# Charge_station.net
KiCad netlist of a schematic drawn in Altium Designer
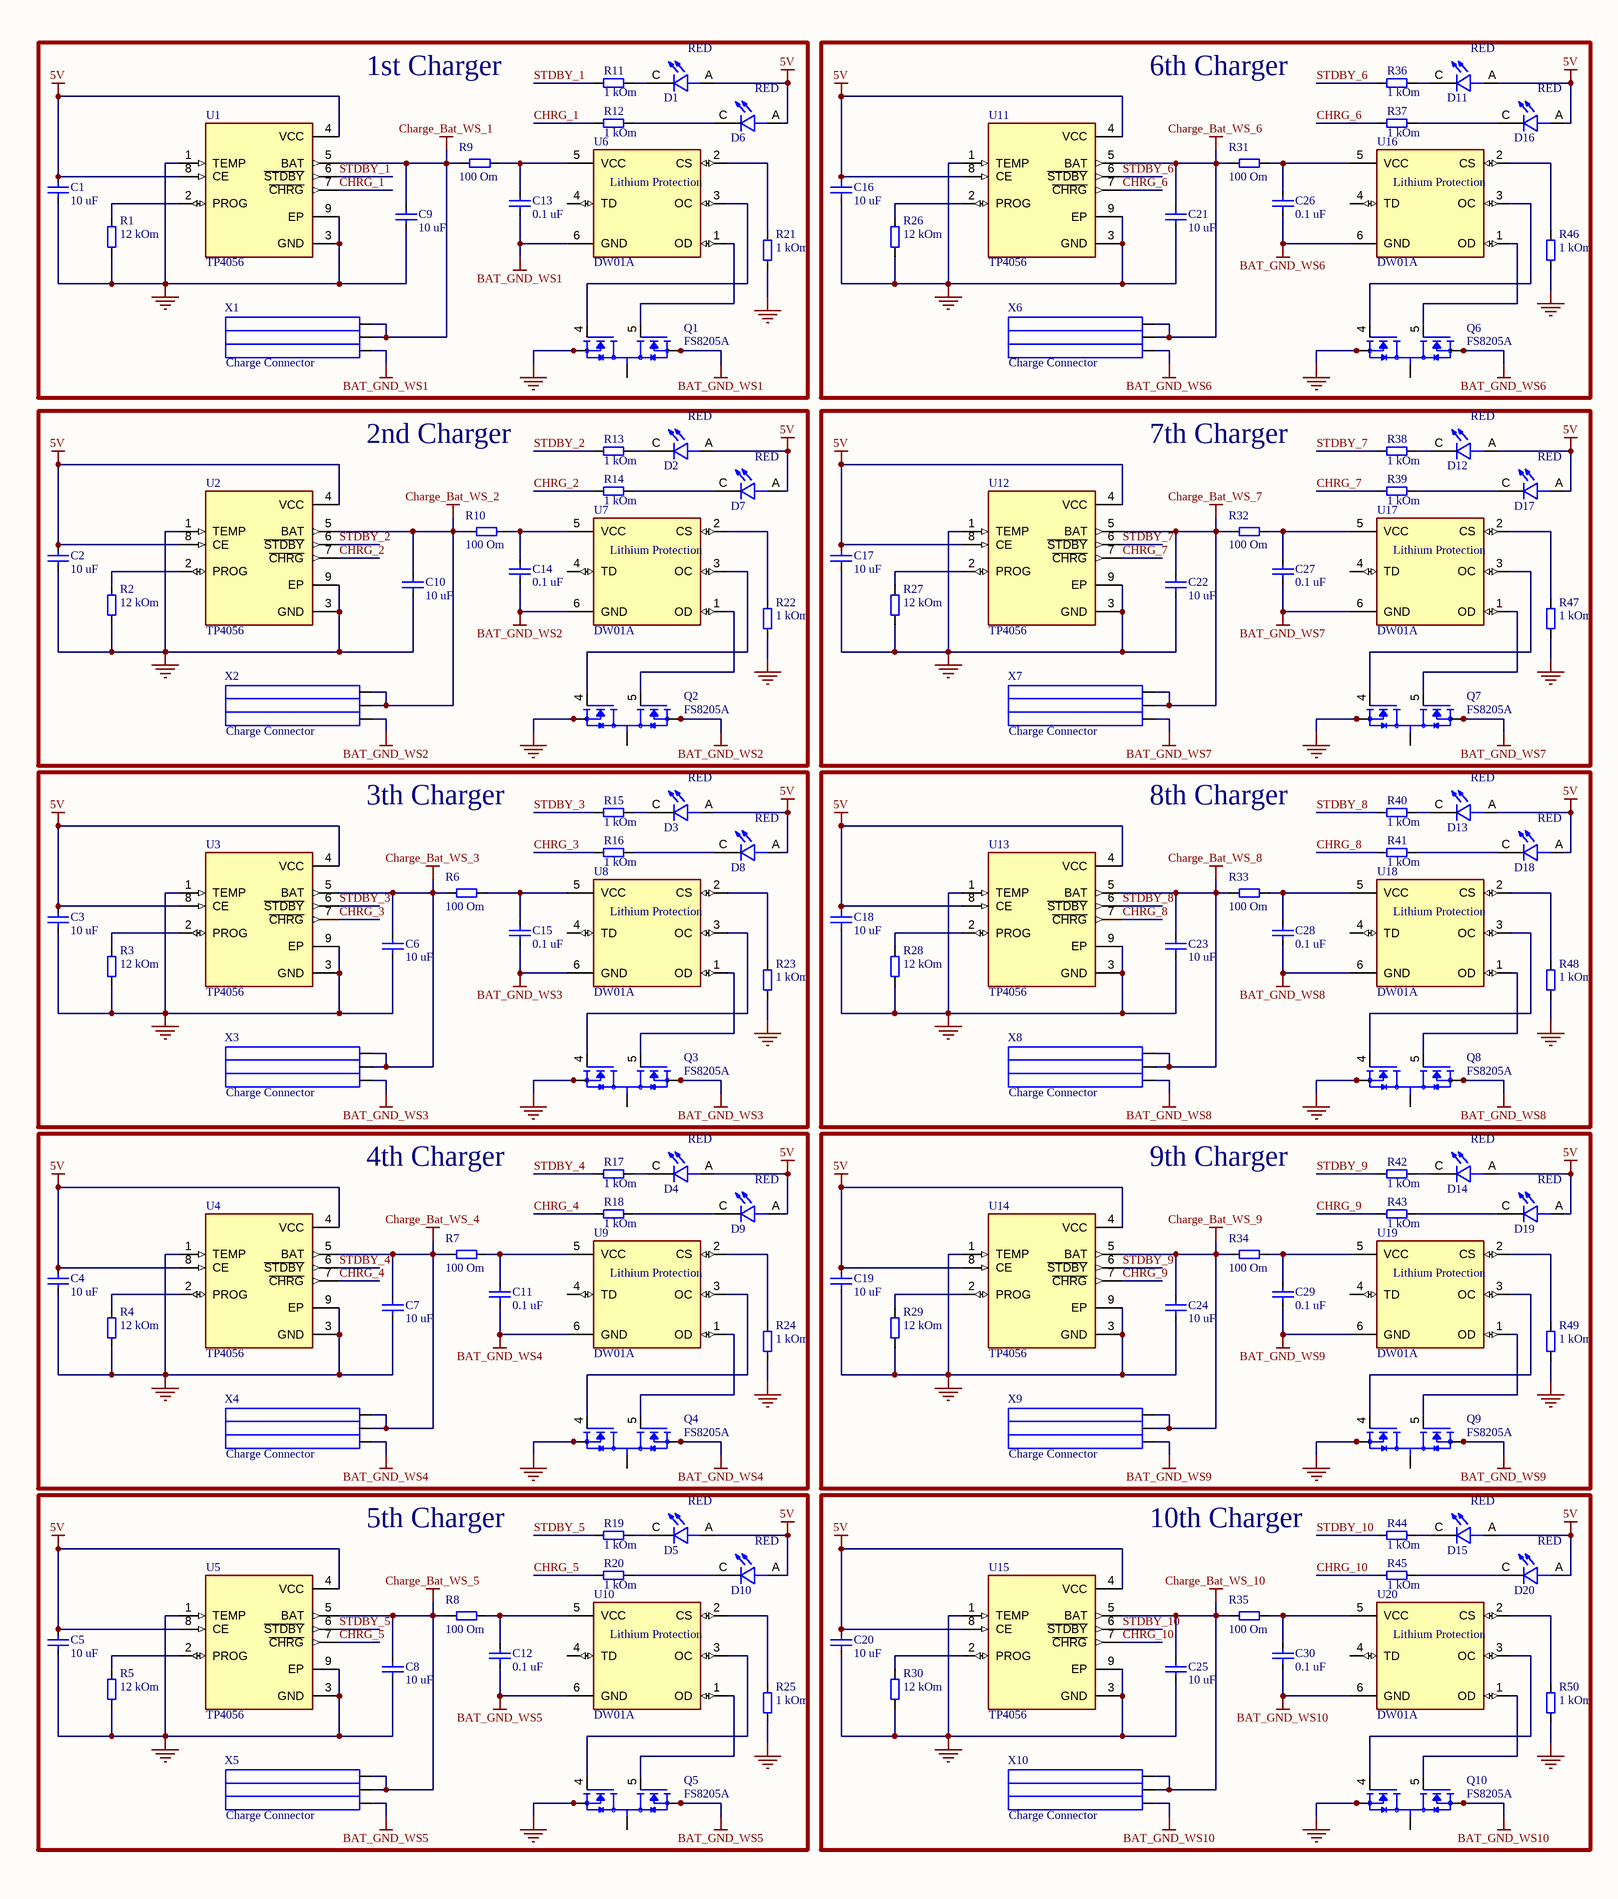
[diagram p0: Charge_station.SchDoc, left]
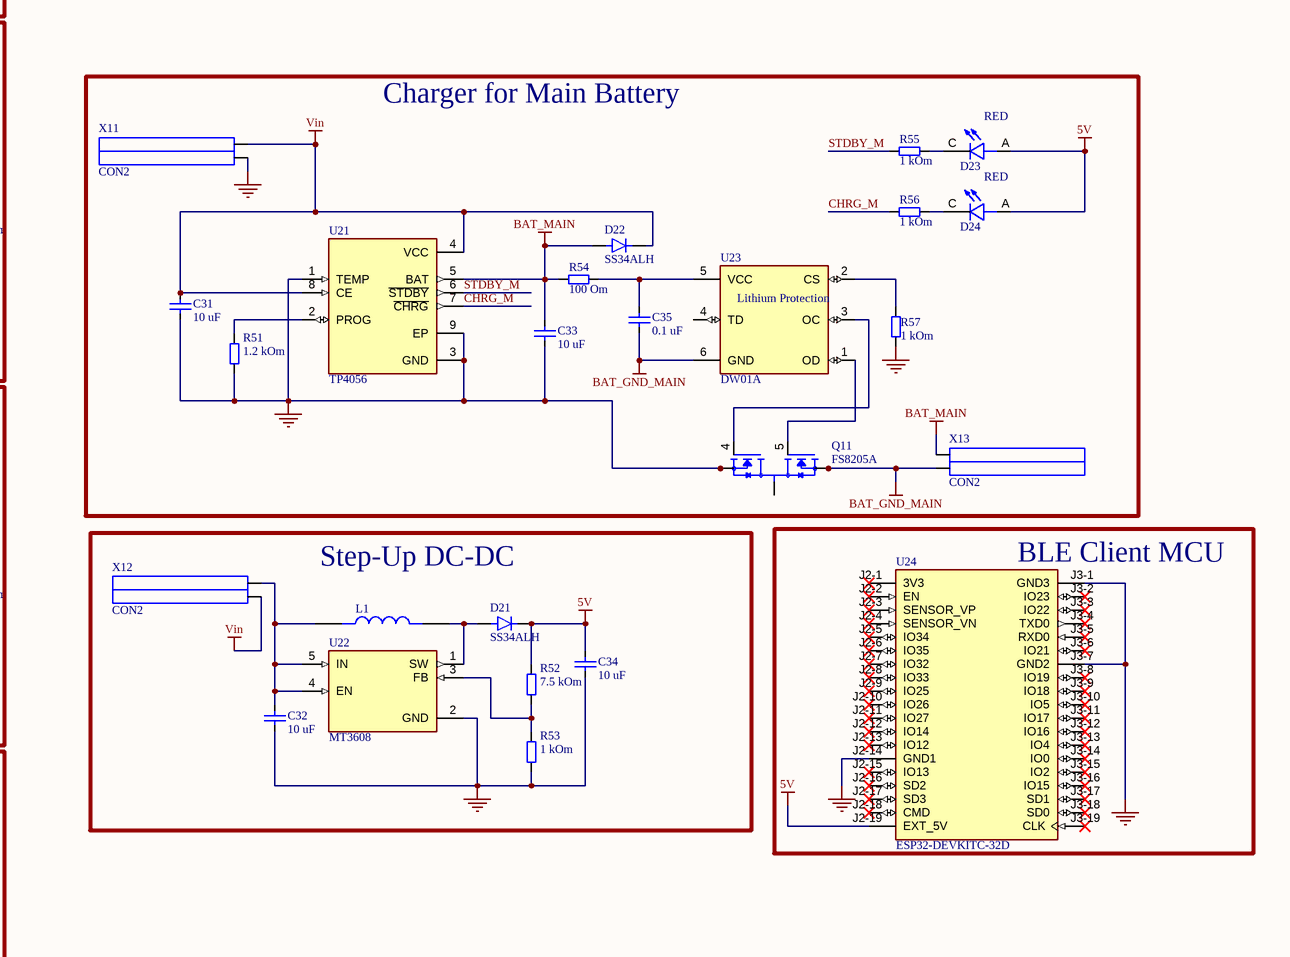
[diagram p1: Charge_station.SchDoc, right]

(export (version "E")
  (design (tool "Eeschema 10.0.6"))
  (components
    (comp (ref "C1")
      (value "10 uF")
      (footprint "CAPC1608X90N")
      (fields
        (field (name "MANUFACTURERPARTNUMBER") "GRM188R61C106MAAL")
        (field (name "MANUFACTURER") "muRata")
        (field (name "Comment") "STD_CAP")
        (field (name "AUTHORCREATION_COMP") "altium_lib_sch_p")
        (field (name "AUTHORMODIFICATION_COMP") "altium_lib_sch_p")
      )
      (libsource (lib "Altium_lib") (part "STD_CAP"))
    )
    (comp (ref "C2")
      (value "10 uF")
      (footprint "CAPC1608X90N")
      (fields
        (field (name "MANUFACTURERPARTNUMBER") "GRM188R61C106MAAL")
        (field (name "MANUFACTURER") "muRata")
        (field (name "Comment") "STD_CAP")
        (field (name "AUTHORCREATION_COMP") "altium_lib_sch_p")
        (field (name "AUTHORMODIFICATION_COMP") "altium_lib_sch_p")
      )
      (libsource (lib "Altium_lib") (part "STD_CAP"))
    )
    (comp (ref "C3")
      (value "10 uF")
      (footprint "CAPC1608X90N")
      (fields
        (field (name "MANUFACTURERPARTNUMBER") "GRM188R61C106MAAL")
        (field (name "MANUFACTURER") "muRata")
        (field (name "Comment") "STD_CAP")
        (field (name "AUTHORCREATION_COMP") "altium_lib_sch_p")
        (field (name "AUTHORMODIFICATION_COMP") "altium_lib_sch_p")
      )
      (libsource (lib "Altium_lib") (part "STD_CAP"))
    )
    (comp (ref "C4")
      (value "10 uF")
      (footprint "CAPC1608X90N")
      (fields
        (field (name "MANUFACTURERPARTNUMBER") "GRM188R61C106MAAL")
        (field (name "MANUFACTURER") "muRata")
        (field (name "Comment") "STD_CAP")
        (field (name "AUTHORCREATION_COMP") "altium_lib_sch_p")
        (field (name "AUTHORMODIFICATION_COMP") "altium_lib_sch_p")
      )
      (libsource (lib "Altium_lib") (part "STD_CAP"))
    )
    (comp (ref "C5")
      (value "10 uF")
      (footprint "CAPC1608X90N")
      (fields
        (field (name "MANUFACTURERPARTNUMBER") "GRM188R61C106MAAL")
        (field (name "MANUFACTURER") "muRata")
        (field (name "Comment") "STD_CAP")
        (field (name "AUTHORCREATION_COMP") "altium_lib_sch_p")
        (field (name "AUTHORMODIFICATION_COMP") "altium_lib_sch_p")
      )
      (libsource (lib "Altium_lib") (part "STD_CAP"))
    )
    (comp (ref "C6")
      (value "10 uF")
      (footprint "CAPC1608X90N")
      (fields
        (field (name "MANUFACTURERPARTNUMBER") "GRM188R61C106MAAL")
        (field (name "MANUFACTURER") "muRata")
        (field (name "Comment") "STD_CAP")
        (field (name "AUTHORCREATION_COMP") "altium_lib_sch_p")
        (field (name "AUTHORMODIFICATION_COMP") "altium_lib_sch_p")
      )
      (libsource (lib "Altium_lib") (part "STD_CAP"))
    )
    (comp (ref "C7")
      (value "10 uF")
      (footprint "CAPC1608X90N")
      (fields
        (field (name "MANUFACTURERPARTNUMBER") "GRM188R61C106MAAL")
        (field (name "MANUFACTURER") "muRata")
        (field (name "Comment") "STD_CAP")
        (field (name "AUTHORCREATION_COMP") "altium_lib_sch_p")
        (field (name "AUTHORMODIFICATION_COMP") "altium_lib_sch_p")
      )
      (libsource (lib "Altium_lib") (part "STD_CAP"))
    )
    (comp (ref "C8")
      (value "10 uF")
      (footprint "CAPC1608X90N")
      (fields
        (field (name "MANUFACTURERPARTNUMBER") "GRM188R61C106MAAL")
        (field (name "MANUFACTURER") "muRata")
        (field (name "Comment") "STD_CAP")
        (field (name "AUTHORCREATION_COMP") "altium_lib_sch_p")
        (field (name "AUTHORMODIFICATION_COMP") "altium_lib_sch_p")
      )
      (libsource (lib "Altium_lib") (part "STD_CAP"))
    )
    (comp (ref "C9")
      (value "10 uF")
      (footprint "CAPC1608X90N")
      (fields
        (field (name "MANUFACTURERPARTNUMBER") "GRM188R61C106MAAL")
        (field (name "MANUFACTURER") "muRata")
        (field (name "Comment") "STD_CAP")
        (field (name "AUTHORCREATION_COMP") "altium_lib_sch_p")
        (field (name "AUTHORMODIFICATION_COMP") "altium_lib_sch_p")
      )
      (libsource (lib "Altium_lib") (part "STD_CAP"))
    )
    (comp (ref "C10")
      (value "10 uF")
      (footprint "CAPC1608X90N")
      (fields
        (field (name "MANUFACTURERPARTNUMBER") "GRM188R61C106MAAL")
        (field (name "MANUFACTURER") "muRata")
        (field (name "Comment") "STD_CAP")
        (field (name "AUTHORCREATION_COMP") "altium_lib_sch_p")
        (field (name "AUTHORMODIFICATION_COMP") "altium_lib_sch_p")
      )
      (libsource (lib "Altium_lib") (part "STD_CAP"))
    )
    (comp (ref "C11")
      (value "0.1 uF")
      (footprint "CAPC1608X90N")
      (fields
        (field (name "MANUFACTURERPARTNUMBER") "C1608X7R1H104K")
        (field (name "MANUFACTURER") "TDK")
        (field (name "Comment") "STD_CAP")
        (field (name "AUTHORCREATION_COMP") "anosova")
        (field (name "AUTHORMODIFICATION_COMP") "anosova")
      )
      (libsource (lib "Altium_lib") (part "STD_CAP"))
    )
    (comp (ref "C12")
      (value "0.1 uF")
      (footprint "CAPC1608X90N")
      (fields
        (field (name "MANUFACTURERPARTNUMBER") "C1608X7R1H104K")
        (field (name "MANUFACTURER") "TDK")
        (field (name "Comment") "STD_CAP")
        (field (name "AUTHORCREATION_COMP") "anosova")
        (field (name "AUTHORMODIFICATION_COMP") "anosova")
      )
      (libsource (lib "Altium_lib") (part "STD_CAP"))
    )
    (comp (ref "C13")
      (value "0.1 uF")
      (footprint "CAPC1608X90N")
      (fields
        (field (name "MANUFACTURERPARTNUMBER") "C1608X7R1H104K")
        (field (name "MANUFACTURER") "TDK")
        (field (name "Comment") "STD_CAP")
        (field (name "AUTHORCREATION_COMP") "anosova")
        (field (name "AUTHORMODIFICATION_COMP") "anosova")
      )
      (libsource (lib "Altium_lib") (part "STD_CAP"))
    )
    (comp (ref "C14")
      (value "0.1 uF")
      (footprint "CAPC1608X90N")
      (fields
        (field (name "MANUFACTURERPARTNUMBER") "C1608X7R1H104K")
        (field (name "MANUFACTURER") "TDK")
        (field (name "Comment") "STD_CAP")
        (field (name "AUTHORCREATION_COMP") "anosova")
        (field (name "AUTHORMODIFICATION_COMP") "anosova")
      )
      (libsource (lib "Altium_lib") (part "STD_CAP"))
    )
    (comp (ref "C15")
      (value "0.1 uF")
      (footprint "CAPC1608X90N")
      (fields
        (field (name "MANUFACTURERPARTNUMBER") "C1608X7R1H104K")
        (field (name "MANUFACTURER") "TDK")
        (field (name "Comment") "STD_CAP")
        (field (name "AUTHORCREATION_COMP") "anosova")
        (field (name "AUTHORMODIFICATION_COMP") "anosova")
      )
      (libsource (lib "Altium_lib") (part "STD_CAP"))
    )
    (comp (ref "C16")
      (value "10 uF")
      (footprint "CAPC1608X90N")
      (fields
        (field (name "MANUFACTURERPARTNUMBER") "GRM188R61C106MAAL")
        (field (name "MANUFACTURER") "muRata")
        (field (name "Comment") "STD_CAP")
        (field (name "AUTHORCREATION_COMP") "altium_lib_sch_p")
        (field (name "AUTHORMODIFICATION_COMP") "altium_lib_sch_p")
      )
      (libsource (lib "Altium_lib") (part "STD_CAP"))
    )
    (comp (ref "C17")
      (value "10 uF")
      (footprint "CAPC1608X90N")
      (fields
        (field (name "MANUFACTURERPARTNUMBER") "GRM188R61C106MAAL")
        (field (name "MANUFACTURER") "muRata")
        (field (name "Comment") "STD_CAP")
        (field (name "AUTHORCREATION_COMP") "altium_lib_sch_p")
        (field (name "AUTHORMODIFICATION_COMP") "altium_lib_sch_p")
      )
      (libsource (lib "Altium_lib") (part "STD_CAP"))
    )
    (comp (ref "C18")
      (value "10 uF")
      (footprint "CAPC1608X90N")
      (fields
        (field (name "MANUFACTURERPARTNUMBER") "GRM188R61C106MAAL")
        (field (name "MANUFACTURER") "muRata")
        (field (name "Comment") "STD_CAP")
        (field (name "AUTHORCREATION_COMP") "altium_lib_sch_p")
        (field (name "AUTHORMODIFICATION_COMP") "altium_lib_sch_p")
      )
      (libsource (lib "Altium_lib") (part "STD_CAP"))
    )
    (comp (ref "C19")
      (value "10 uF")
      (footprint "CAPC1608X90N")
      (fields
        (field (name "MANUFACTURERPARTNUMBER") "GRM188R61C106MAAL")
        (field (name "MANUFACTURER") "muRata")
        (field (name "Comment") "STD_CAP")
        (field (name "AUTHORCREATION_COMP") "altium_lib_sch_p")
        (field (name "AUTHORMODIFICATION_COMP") "altium_lib_sch_p")
      )
      (libsource (lib "Altium_lib") (part "STD_CAP"))
    )
    (comp (ref "C20")
      (value "10 uF")
      (footprint "CAPC1608X90N")
      (fields
        (field (name "MANUFACTURERPARTNUMBER") "GRM188R61C106MAAL")
        (field (name "MANUFACTURER") "muRata")
        (field (name "Comment") "STD_CAP")
        (field (name "AUTHORCREATION_COMP") "altium_lib_sch_p")
        (field (name "AUTHORMODIFICATION_COMP") "altium_lib_sch_p")
      )
      (libsource (lib "Altium_lib") (part "STD_CAP"))
    )
    (comp (ref "C21")
      (value "10 uF")
      (footprint "CAPC1608X90N")
      (fields
        (field (name "MANUFACTURERPARTNUMBER") "GRM188R61C106MAAL")
        (field (name "MANUFACTURER") "muRata")
        (field (name "Comment") "STD_CAP")
        (field (name "AUTHORCREATION_COMP") "altium_lib_sch_p")
        (field (name "AUTHORMODIFICATION_COMP") "altium_lib_sch_p")
      )
      (libsource (lib "Altium_lib") (part "STD_CAP"))
    )
    (comp (ref "C22")
      (value "10 uF")
      (footprint "CAPC1608X90N")
      (fields
        (field (name "MANUFACTURERPARTNUMBER") "GRM188R61C106MAAL")
        (field (name "MANUFACTURER") "muRata")
        (field (name "Comment") "STD_CAP")
        (field (name "AUTHORCREATION_COMP") "altium_lib_sch_p")
        (field (name "AUTHORMODIFICATION_COMP") "altium_lib_sch_p")
      )
      (libsource (lib "Altium_lib") (part "STD_CAP"))
    )
    (comp (ref "C23")
      (value "10 uF")
      (footprint "CAPC1608X90N")
      (fields
        (field (name "MANUFACTURERPARTNUMBER") "GRM188R61C106MAAL")
        (field (name "MANUFACTURER") "muRata")
        (field (name "Comment") "STD_CAP")
        (field (name "AUTHORCREATION_COMP") "altium_lib_sch_p")
        (field (name "AUTHORMODIFICATION_COMP") "altium_lib_sch_p")
      )
      (libsource (lib "Altium_lib") (part "STD_CAP"))
    )
    (comp (ref "C24")
      (value "10 uF")
      (footprint "CAPC1608X90N")
      (fields
        (field (name "MANUFACTURERPARTNUMBER") "GRM188R61C106MAAL")
        (field (name "MANUFACTURER") "muRata")
        (field (name "Comment") "STD_CAP")
        (field (name "AUTHORCREATION_COMP") "altium_lib_sch_p")
        (field (name "AUTHORMODIFICATION_COMP") "altium_lib_sch_p")
      )
      (libsource (lib "Altium_lib") (part "STD_CAP"))
    )
    (comp (ref "C25")
      (value "10 uF")
      (footprint "CAPC1608X90N")
      (fields
        (field (name "MANUFACTURERPARTNUMBER") "GRM188R61C106MAAL")
        (field (name "MANUFACTURER") "muRata")
        (field (name "Comment") "STD_CAP")
        (field (name "AUTHORCREATION_COMP") "altium_lib_sch_p")
        (field (name "AUTHORMODIFICATION_COMP") "altium_lib_sch_p")
      )
      (libsource (lib "Altium_lib") (part "STD_CAP"))
    )
    (comp (ref "C26")
      (value "0.1 uF")
      (footprint "CAPC1608X90N")
      (fields
        (field (name "MANUFACTURERPARTNUMBER") "C1608X7R1H104K")
        (field (name "MANUFACTURER") "TDK")
        (field (name "Comment") "STD_CAP")
        (field (name "AUTHORCREATION_COMP") "anosova")
        (field (name "AUTHORMODIFICATION_COMP") "anosova")
      )
      (libsource (lib "Altium_lib") (part "STD_CAP"))
    )
    (comp (ref "C27")
      (value "0.1 uF")
      (footprint "CAPC1608X90N")
      (fields
        (field (name "MANUFACTURERPARTNUMBER") "C1608X7R1H104K")
        (field (name "MANUFACTURER") "TDK")
        (field (name "Comment") "STD_CAP")
        (field (name "AUTHORCREATION_COMP") "anosova")
        (field (name "AUTHORMODIFICATION_COMP") "anosova")
      )
      (libsource (lib "Altium_lib") (part "STD_CAP"))
    )
    (comp (ref "C28")
      (value "0.1 uF")
      (footprint "CAPC1608X90N")
      (fields
        (field (name "MANUFACTURERPARTNUMBER") "C1608X7R1H104K")
        (field (name "MANUFACTURER") "TDK")
        (field (name "Comment") "STD_CAP")
        (field (name "AUTHORCREATION_COMP") "anosova")
        (field (name "AUTHORMODIFICATION_COMP") "anosova")
      )
      (libsource (lib "Altium_lib") (part "STD_CAP"))
    )
    (comp (ref "C29")
      (value "0.1 uF")
      (footprint "CAPC1608X90N")
      (fields
        (field (name "MANUFACTURERPARTNUMBER") "C1608X7R1H104K")
        (field (name "MANUFACTURER") "TDK")
        (field (name "Comment") "STD_CAP")
        (field (name "AUTHORCREATION_COMP") "anosova")
        (field (name "AUTHORMODIFICATION_COMP") "anosova")
      )
      (libsource (lib "Altium_lib") (part "STD_CAP"))
    )
    (comp (ref "C30")
      (value "0.1 uF")
      (footprint "CAPC1608X90N")
      (fields
        (field (name "MANUFACTURERPARTNUMBER") "C1608X7R1H104K")
        (field (name "MANUFACTURER") "TDK")
        (field (name "Comment") "STD_CAP")
        (field (name "AUTHORCREATION_COMP") "anosova")
        (field (name "AUTHORMODIFICATION_COMP") "anosova")
      )
      (libsource (lib "Altium_lib") (part "STD_CAP"))
    )
    (comp (ref "C31")
      (value "10 uF")
      (footprint "CAPC1608X90N")
      (fields
        (field (name "MANUFACTURERPARTNUMBER") "GRM188R61C106MAAL")
        (field (name "MANUFACTURER") "muRata")
        (field (name "Comment") "STD_CAP")
        (field (name "AUTHORCREATION_COMP") "altium_lib_sch_p")
        (field (name "AUTHORMODIFICATION_COMP") "altium_lib_sch_p")
      )
      (libsource (lib "Altium_lib") (part "STD_CAP"))
    )
    (comp (ref "C32")
      (value "10 uF")
      (footprint "CAPC2012X120N")
      (fields
        (field (name "MANUFACTURERPARTNUMBER") "GRM21BR71A106KE51L")
        (field (name "MANUFACTURER") "muRata")
        (field (name "Comment") "STD_CAP")
      )
      (libsource (lib "Altium_lib") (part "STD_CAP"))
    )
    (comp (ref "C33")
      (value "10 uF")
      (footprint "CAPC1608X90N")
      (fields
        (field (name "MANUFACTURERPARTNUMBER") "GRM188R61C106MAAL")
        (field (name "MANUFACTURER") "muRata")
        (field (name "Comment") "STD_CAP")
        (field (name "AUTHORCREATION_COMP") "altium_lib_sch_p")
        (field (name "AUTHORMODIFICATION_COMP") "altium_lib_sch_p")
      )
      (libsource (lib "Altium_lib") (part "STD_CAP"))
    )
    (comp (ref "C34")
      (value "10 uF")
      (footprint "CAPC2012X120N")
      (fields
        (field (name "MANUFACTURERPARTNUMBER") "GRM21BR71A106KE51L")
        (field (name "MANUFACTURER") "muRata")
        (field (name "Comment") "STD_CAP")
      )
      (libsource (lib "Altium_lib") (part "STD_CAP"))
    )
    (comp (ref "C35")
      (value "0.1 uF")
      (footprint "CAPC1608X90N")
      (fields
        (field (name "MANUFACTURERPARTNUMBER") "C1608X7R1H104K")
        (field (name "MANUFACTURER") "TDK")
        (field (name "Comment") "STD_CAP")
        (field (name "AUTHORCREATION_COMP") "anosova")
        (field (name "AUTHORMODIFICATION_COMP") "anosova")
      )
      (libsource (lib "Altium_lib") (part "STD_CAP"))
    )
    (comp (ref "D1")
      (value "7012X1")
      (footprint "LED_KPT-1608ZGC")
      (description "Red - LED Indication - Discrete 1.7V 0805 (2012 Metric)")
      (fields (field (name "MF") "VCC"))
      (libsource (lib "7012X1") (part "7012X1"))
    )
    (comp (ref "D2")
      (value "7012X1")
      (footprint "LED_KPT-1608ZGC")
      (description "Red - LED Indication - Discrete 1.7V 0805 (2012 Metric)")
      (fields (field (name "MF") "VCC"))
      (libsource (lib "7012X1") (part "7012X1"))
    )
    (comp (ref "D3")
      (value "7012X1")
      (footprint "LED_KPT-1608ZGC")
      (description "Red - LED Indication - Discrete 1.7V 0805 (2012 Metric)")
      (fields (field (name "MF") "VCC"))
      (libsource (lib "7012X1") (part "7012X1"))
    )
    (comp (ref "D4")
      (value "7012X1")
      (footprint "LED_KPT-1608ZGC")
      (description "Red - LED Indication - Discrete 1.7V 0805 (2012 Metric)")
      (fields (field (name "MF") "VCC"))
      (libsource (lib "7012X1") (part "7012X1"))
    )
    (comp (ref "D5")
      (value "7012X1")
      (footprint "LED_KPT-1608ZGC")
      (description "Red - LED Indication - Discrete 1.7V 0805 (2012 Metric)")
      (fields (field (name "MF") "VCC"))
      (libsource (lib "7012X1") (part "7012X1"))
    )
    (comp (ref "D6")
      (value "7012X1")
      (footprint "LED_KPT-1608ZGC")
      (description "Red - LED Indication - Discrete 1.7V 0805 (2012 Metric)")
      (fields (field (name "MF") "VCC"))
      (libsource (lib "7012X1") (part "7012X1"))
    )
    (comp (ref "D7")
      (value "7012X1")
      (footprint "LED_KPT-1608ZGC")
      (description "Red - LED Indication - Discrete 1.7V 0805 (2012 Metric)")
      (fields (field (name "MF") "VCC"))
      (libsource (lib "7012X1") (part "7012X1"))
    )
    (comp (ref "D8")
      (value "7012X1")
      (footprint "LED_KPT-1608ZGC")
      (description "Red - LED Indication - Discrete 1.7V 0805 (2012 Metric)")
      (fields (field (name "MF") "VCC"))
      (libsource (lib "7012X1") (part "7012X1"))
    )
    (comp (ref "D9")
      (value "7012X1")
      (footprint "LED_KPT-1608ZGC")
      (description "Red - LED Indication - Discrete 1.7V 0805 (2012 Metric)")
      (fields (field (name "MF") "VCC"))
      (libsource (lib "7012X1") (part "7012X1"))
    )
    (comp (ref "D10")
      (value "7012X1")
      (footprint "LED_KPT-1608ZGC")
      (description "Red - LED Indication - Discrete 1.7V 0805 (2012 Metric)")
      (fields (field (name "MF") "VCC"))
      (libsource (lib "7012X1") (part "7012X1"))
    )
    (comp (ref "D11")
      (value "7012X1")
      (footprint "LED_KPT-1608ZGC")
      (description "Red - LED Indication - Discrete 1.7V 0805 (2012 Metric)")
      (fields (field (name "MF") "VCC"))
      (libsource (lib "7012X1") (part "7012X1"))
    )
    (comp (ref "D12")
      (value "7012X1")
      (footprint "LED_KPT-1608ZGC")
      (description "Red - LED Indication - Discrete 1.7V 0805 (2012 Metric)")
      (fields (field (name "MF") "VCC"))
      (libsource (lib "7012X1") (part "7012X1"))
    )
    (comp (ref "D13")
      (value "7012X1")
      (footprint "LED_KPT-1608ZGC")
      (description "Red - LED Indication - Discrete 1.7V 0805 (2012 Metric)")
      (fields (field (name "MF") "VCC"))
      (libsource (lib "7012X1") (part "7012X1"))
    )
    (comp (ref "D14")
      (value "7012X1")
      (footprint "LED_KPT-1608ZGC")
      (description "Red - LED Indication - Discrete 1.7V 0805 (2012 Metric)")
      (fields (field (name "MF") "VCC"))
      (libsource (lib "7012X1") (part "7012X1"))
    )
    (comp (ref "D15")
      (value "7012X1")
      (footprint "LED_KPT-1608ZGC")
      (description "Red - LED Indication - Discrete 1.7V 0805 (2012 Metric)")
      (fields (field (name "MF") "VCC"))
      (libsource (lib "7012X1") (part "7012X1"))
    )
    (comp (ref "D16")
      (value "7012X1")
      (footprint "LED_KPT-1608ZGC")
      (description "Red - LED Indication - Discrete 1.7V 0805 (2012 Metric)")
      (fields (field (name "MF") "VCC"))
      (libsource (lib "7012X1") (part "7012X1"))
    )
    (comp (ref "D17")
      (value "7012X1")
      (footprint "LED_KPT-1608ZGC")
      (description "Red - LED Indication - Discrete 1.7V 0805 (2012 Metric)")
      (fields (field (name "MF") "VCC"))
      (libsource (lib "7012X1") (part "7012X1"))
    )
    (comp (ref "D18")
      (value "7012X1")
      (footprint "LED_KPT-1608ZGC")
      (description "Red - LED Indication - Discrete 1.7V 0805 (2012 Metric)")
      (fields (field (name "MF") "VCC"))
      (libsource (lib "7012X1") (part "7012X1"))
    )
    (comp (ref "D19")
      (value "7012X1")
      (footprint "LED_KPT-1608ZGC")
      (description "Red - LED Indication - Discrete 1.7V 0805 (2012 Metric)")
      (fields (field (name "MF") "VCC"))
      (libsource (lib "7012X1") (part "7012X1"))
    )
    (comp (ref "D20")
      (value "7012X1")
      (footprint "LED_KPT-1608ZGC")
      (description "Red - LED Indication - Discrete 1.7V 0805 (2012 Metric)")
      (fields (field (name "MF") "VCC"))
      (libsource (lib "7012X1") (part "7012X1"))
    )
    (comp (ref "D21")
      (value "SS34ALH")
      (footprint "SODFL5226X100N")
      (description "3A, 40V, Schottky Rectifier")
      (fields (field (name "MF") "Taiwan Semiconductor"))
      (libsource (lib "SCH_Wearing_sensor") (part "SS34ALH"))
    )
    (comp (ref "D22")
      (value "SS34ALH")
      (footprint "SODFL5226X100N")
      (description "3A, 40V, Schottky Rectifier")
      (fields (field (name "MF") "Taiwan Semiconductor"))
      (libsource (lib "SCH_Wearing_sensor") (part "SS34ALH"))
    )
    (comp (ref "D23")
      (value "7012X1")
      (footprint "LED_KPT-1608ZGC")
      (description "Red - LED Indication - Discrete 1.7V 0805 (2012 Metric)")
      (fields (field (name "MF") "VCC"))
      (libsource (lib "7012X1") (part "7012X1"))
    )
    (comp (ref "D24")
      (value "7012X1")
      (footprint "LED_KPT-1608ZGC")
      (description "Red - LED Indication - Discrete 1.7V 0805 (2012 Metric)")
      (fields (field (name "MF") "VCC"))
      (libsource (lib "7012X1") (part "7012X1"))
    )
    (comp (ref "L1")
      (value "B82464G4223M000")
      (footprint "IND_B82464G4223M000")
      (fields (field (name "MF") "TDK ELECTRONICS"))
      (libsource (lib "SCH_Wearing_sensor") (part "B82464G4223M000"))
    )
    (comp (ref "Q1")
      (value "FS8205A")
      (footprint "SOP65P640X120-8N")
      (fields (field (name "MF") "Fortune Semiconductor"))
      (libsource (lib "SCH_Wearing_sensor") (part "FS8205A"))
    )
    (comp (ref "Q2")
      (value "FS8205A")
      (footprint "SOP65P640X120-8N")
      (fields (field (name "MF") "Fortune Semiconductor"))
      (libsource (lib "SCH_Wearing_sensor") (part "FS8205A"))
    )
    (comp (ref "Q3")
      (value "FS8205A")
      (footprint "SOP65P640X120-8N")
      (fields (field (name "MF") "Fortune Semiconductor"))
      (libsource (lib "SCH_Wearing_sensor") (part "FS8205A"))
    )
    (comp (ref "Q4")
      (value "FS8205A")
      (footprint "SOP65P640X120-8N")
      (fields (field (name "MF") "Fortune Semiconductor"))
      (libsource (lib "SCH_Wearing_sensor") (part "FS8205A"))
    )
    (comp (ref "Q5")
      (value "FS8205A")
      (footprint "SOP65P640X120-8N")
      (fields (field (name "MF") "Fortune Semiconductor"))
      (libsource (lib "SCH_Wearing_sensor") (part "FS8205A"))
    )
    (comp (ref "Q6")
      (value "FS8205A")
      (footprint "SOP65P640X120-8N")
      (fields (field (name "MF") "Fortune Semiconductor"))
      (libsource (lib "SCH_Wearing_sensor") (part "FS8205A"))
    )
    (comp (ref "Q7")
      (value "FS8205A")
      (footprint "SOP65P640X120-8N")
      (fields (field (name "MF") "Fortune Semiconductor"))
      (libsource (lib "SCH_Wearing_sensor") (part "FS8205A"))
    )
    (comp (ref "Q8")
      (value "FS8205A")
      (footprint "SOP65P640X120-8N")
      (fields (field (name "MF") "Fortune Semiconductor"))
      (libsource (lib "SCH_Wearing_sensor") (part "FS8205A"))
    )
    (comp (ref "Q9")
      (value "FS8205A")
      (footprint "SOP65P640X120-8N")
      (fields (field (name "MF") "Fortune Semiconductor"))
      (libsource (lib "SCH_Wearing_sensor") (part "FS8205A"))
    )
    (comp (ref "Q10")
      (value "FS8205A")
      (footprint "SOP65P640X120-8N")
      (fields (field (name "MF") "Fortune Semiconductor"))
      (libsource (lib "SCH_Wearing_sensor") (part "FS8205A"))
    )
    (comp (ref "Q11")
      (value "FS8205A")
      (footprint "SOP65P640X120-8N")
      (fields (field (name "MF") "Fortune Semiconductor"))
      (libsource (lib "SCH_Wearing_sensor") (part "FS8205A"))
    )
    (comp (ref "R1")
      (value "12 kOm")
      (footprint "RESC1608X50AN")
      (fields
        (field (name "MANUFACTURERPARTNUMBER") "RC0603JR-0712KL")
        (field (name "MANUFACTURER") "Yageo")
        (field (name "Comment") "STD_RES")
      )
      (libsource (lib "") (part "STD_RES_2"))
    )
    (comp (ref "R2")
      (value "12 kOm")
      (footprint "RESC1608X50AN")
      (fields
        (field (name "MANUFACTURERPARTNUMBER") "RC0603JR-0712KL")
        (field (name "MANUFACTURER") "Yageo")
        (field (name "Comment") "STD_RES")
      )
      (libsource (lib "") (part "STD_RES_2"))
    )
    (comp (ref "R3")
      (value "12 kOm")
      (footprint "RESC1608X50AN")
      (fields
        (field (name "MANUFACTURERPARTNUMBER") "RC0603JR-0712KL")
        (field (name "MANUFACTURER") "Yageo")
        (field (name "Comment") "STD_RES")
      )
      (libsource (lib "") (part "STD_RES_2"))
    )
    (comp (ref "R4")
      (value "12 kOm")
      (footprint "RESC1608X50AN")
      (fields
        (field (name "MANUFACTURERPARTNUMBER") "RC0603JR-0712KL")
        (field (name "MANUFACTURER") "Yageo")
        (field (name "Comment") "STD_RES")
      )
      (libsource (lib "") (part "STD_RES_2"))
    )
    (comp (ref "R5")
      (value "12 kOm")
      (footprint "RESC1608X50AN")
      (fields
        (field (name "MANUFACTURERPARTNUMBER") "RC0603JR-0712KL")
        (field (name "MANUFACTURER") "Yageo")
        (field (name "Comment") "STD_RES")
      )
      (libsource (lib "") (part "STD_RES_2"))
    )
    (comp (ref "R6")
      (value "100 Om")
      (footprint "RESC1608X50AN")
      (fields
        (field (name "MANUFACTURERPARTNUMBER") "RC0603FR-07100RL")
        (field (name "MANUFACTURER") "Yageo")
        (field (name "Comment") "STD_RES")
      )
      (libsource (lib "Altium_lib") (part "STD_RES"))
    )
    (comp (ref "R7")
      (value "100 Om")
      (footprint "RESC1608X50AN")
      (fields
        (field (name "MANUFACTURERPARTNUMBER") "RC0603FR-07100RL")
        (field (name "MANUFACTURER") "Yageo")
        (field (name "Comment") "STD_RES")
      )
      (libsource (lib "Altium_lib") (part "STD_RES"))
    )
    (comp (ref "R8")
      (value "100 Om")
      (footprint "RESC1608X50AN")
      (fields
        (field (name "MANUFACTURERPARTNUMBER") "RC0603FR-07100RL")
        (field (name "MANUFACTURER") "Yageo")
        (field (name "Comment") "STD_RES")
      )
      (libsource (lib "Altium_lib") (part "STD_RES"))
    )
    (comp (ref "R9")
      (value "100 Om")
      (footprint "RESC1608X50AN")
      (fields
        (field (name "MANUFACTURERPARTNUMBER") "RC0603FR-07100RL")
        (field (name "MANUFACTURER") "Yageo")
        (field (name "Comment") "STD_RES")
      )
      (libsource (lib "Altium_lib") (part "STD_RES"))
    )
    (comp (ref "R10")
      (value "100 Om")
      (footprint "RESC1608X50AN")
      (fields
        (field (name "MANUFACTURERPARTNUMBER") "RC0603FR-07100RL")
        (field (name "MANUFACTURER") "Yageo")
        (field (name "Comment") "STD_RES")
      )
      (libsource (lib "Altium_lib") (part "STD_RES"))
    )
    (comp (ref "R11")
      (value "1 kOm")
      (footprint "R0603")
      (fields
        (field (name "MANUFACTURERPARTNUMBER") "RC0603FR-071K00L")
        (field (name "MANUFACTURER") "Yageo")
        (field (name "Comment") "STD_RES")
      )
      (libsource (lib "") (part "STD_RES_1"))
    )
    (comp (ref "R12")
      (value "1 kOm")
      (footprint "R0603")
      (fields
        (field (name "MANUFACTURERPARTNUMBER") "RC0603FR-071K00L")
        (field (name "MANUFACTURER") "Yageo")
        (field (name "Comment") "STD_RES")
      )
      (libsource (lib "") (part "STD_RES_1"))
    )
    (comp (ref "R13")
      (value "1 kOm")
      (footprint "R0603")
      (fields
        (field (name "MANUFACTURERPARTNUMBER") "RC0603FR-071K00L")
        (field (name "MANUFACTURER") "Yageo")
        (field (name "Comment") "STD_RES")
      )
      (libsource (lib "") (part "STD_RES_1"))
    )
    (comp (ref "R14")
      (value "1 kOm")
      (footprint "R0603")
      (fields
        (field (name "MANUFACTURERPARTNUMBER") "RC0603FR-071K00L")
        (field (name "MANUFACTURER") "Yageo")
        (field (name "Comment") "STD_RES")
      )
      (libsource (lib "") (part "STD_RES_1"))
    )
    (comp (ref "R15")
      (value "1 kOm")
      (footprint "R0603")
      (fields
        (field (name "MANUFACTURERPARTNUMBER") "RC0603FR-071K00L")
        (field (name "MANUFACTURER") "Yageo")
        (field (name "Comment") "STD_RES")
      )
      (libsource (lib "") (part "STD_RES_1"))
    )
    (comp (ref "R16")
      (value "1 kOm")
      (footprint "R0603")
      (fields
        (field (name "MANUFACTURERPARTNUMBER") "RC0603FR-071K00L")
        (field (name "MANUFACTURER") "Yageo")
        (field (name "Comment") "STD_RES")
      )
      (libsource (lib "") (part "STD_RES_1"))
    )
    (comp (ref "R17")
      (value "1 kOm")
      (footprint "R0603")
      (fields
        (field (name "MANUFACTURERPARTNUMBER") "RC0603FR-071K00L")
        (field (name "MANUFACTURER") "Yageo")
        (field (name "Comment") "STD_RES")
      )
      (libsource (lib "") (part "STD_RES_1"))
    )
    (comp (ref "R18")
      (value "1 kOm")
      (footprint "R0603")
      (fields
        (field (name "MANUFACTURERPARTNUMBER") "RC0603FR-071K00L")
        (field (name "MANUFACTURER") "Yageo")
        (field (name "Comment") "STD_RES")
      )
      (libsource (lib "") (part "STD_RES_1"))
    )
    (comp (ref "R19")
      (value "1 kOm")
      (footprint "R0603")
      (fields
        (field (name "MANUFACTURERPARTNUMBER") "RC0603FR-071K00L")
        (field (name "MANUFACTURER") "Yageo")
        (field (name "Comment") "STD_RES")
      )
      (libsource (lib "") (part "STD_RES_1"))
    )
    (comp (ref "R20")
      (value "1 kOm")
      (footprint "R0603")
      (fields
        (field (name "MANUFACTURERPARTNUMBER") "RC0603FR-071K00L")
        (field (name "MANUFACTURER") "Yageo")
        (field (name "Comment") "STD_RES")
      )
      (libsource (lib "") (part "STD_RES_1"))
    )
    (comp (ref "R21")
      (value "1 kOm")
      (footprint "RESC1608X50AN")
      (fields
        (field (name "MANUFACTURERPARTNUMBER") "RC0603FR-071K00L")
        (field (name "MANUFACTURER") "Yageo")
        (field (name "Comment") "STD_RES")
      )
      (libsource (lib "") (part "STD_RES_2"))
    )
    (comp (ref "R22")
      (value "1 kOm")
      (footprint "RESC1608X50AN")
      (fields
        (field (name "MANUFACTURERPARTNUMBER") "RC0603FR-071K00L")
        (field (name "MANUFACTURER") "Yageo")
        (field (name "Comment") "STD_RES")
      )
      (libsource (lib "") (part "STD_RES_2"))
    )
    (comp (ref "R23")
      (value "1 kOm")
      (footprint "RESC1608X50AN")
      (fields
        (field (name "MANUFACTURERPARTNUMBER") "RC0603FR-071K00L")
        (field (name "MANUFACTURER") "Yageo")
        (field (name "Comment") "STD_RES")
      )
      (libsource (lib "") (part "STD_RES_2"))
    )
    (comp (ref "R24")
      (value "1 kOm")
      (footprint "RESC1608X50AN")
      (fields
        (field (name "MANUFACTURERPARTNUMBER") "RC0603FR-071K00L")
        (field (name "MANUFACTURER") "Yageo")
        (field (name "Comment") "STD_RES")
      )
      (libsource (lib "") (part "STD_RES_2"))
    )
    (comp (ref "R25")
      (value "1 kOm")
      (footprint "RESC1608X50AN")
      (fields
        (field (name "MANUFACTURERPARTNUMBER") "RC0603FR-071K00L")
        (field (name "MANUFACTURER") "Yageo")
        (field (name "Comment") "STD_RES")
      )
      (libsource (lib "") (part "STD_RES_2"))
    )
    (comp (ref "R26")
      (value "12 kOm")
      (footprint "RESC1608X50AN")
      (fields
        (field (name "MANUFACTURERPARTNUMBER") "RC0603JR-0712KL")
        (field (name "MANUFACTURER") "Yageo")
        (field (name "Comment") "STD_RES")
      )
      (libsource (lib "") (part "STD_RES_2"))
    )
    (comp (ref "R27")
      (value "12 kOm")
      (footprint "RESC1608X50AN")
      (fields
        (field (name "MANUFACTURERPARTNUMBER") "RC0603JR-0712KL")
        (field (name "MANUFACTURER") "Yageo")
        (field (name "Comment") "STD_RES")
      )
      (libsource (lib "") (part "STD_RES_2"))
    )
    (comp (ref "R28")
      (value "12 kOm")
      (footprint "RESC1608X50AN")
      (fields
        (field (name "MANUFACTURERPARTNUMBER") "RC0603JR-0712KL")
        (field (name "MANUFACTURER") "Yageo")
        (field (name "Comment") "STD_RES")
      )
      (libsource (lib "") (part "STD_RES_2"))
    )
    (comp (ref "R29")
      (value "12 kOm")
      (footprint "RESC1608X50AN")
      (fields
        (field (name "MANUFACTURERPARTNUMBER") "RC0603JR-0712KL")
        (field (name "MANUFACTURER") "Yageo")
        (field (name "Comment") "STD_RES")
      )
      (libsource (lib "") (part "STD_RES_2"))
    )
    (comp (ref "R30")
      (value "12 kOm")
      (footprint "RESC1608X50AN")
      (fields
        (field (name "MANUFACTURERPARTNUMBER") "RC0603JR-0712KL")
        (field (name "MANUFACTURER") "Yageo")
        (field (name "Comment") "STD_RES")
      )
      (libsource (lib "") (part "STD_RES_2"))
    )
    (comp (ref "R31")
      (value "100 Om")
      (footprint "RESC1608X50AN")
      (fields
        (field (name "MANUFACTURERPARTNUMBER") "RC0603FR-07100RL")
        (field (name "MANUFACTURER") "Yageo")
        (field (name "Comment") "STD_RES")
      )
      (libsource (lib "Altium_lib") (part "STD_RES"))
    )
    (comp (ref "R32")
      (value "100 Om")
      (footprint "RESC1608X50AN")
      (fields
        (field (name "MANUFACTURERPARTNUMBER") "RC0603FR-07100RL")
        (field (name "MANUFACTURER") "Yageo")
        (field (name "Comment") "STD_RES")
      )
      (libsource (lib "Altium_lib") (part "STD_RES"))
    )
    (comp (ref "R33")
      (value "100 Om")
      (footprint "RESC1608X50AN")
      (fields
        (field (name "MANUFACTURERPARTNUMBER") "RC0603FR-07100RL")
        (field (name "MANUFACTURER") "Yageo")
        (field (name "Comment") "STD_RES")
      )
      (libsource (lib "Altium_lib") (part "STD_RES"))
    )
    (comp (ref "R34")
      (value "100 Om")
      (footprint "RESC1608X50AN")
      (fields
        (field (name "MANUFACTURERPARTNUMBER") "RC0603FR-07100RL")
        (field (name "MANUFACTURER") "Yageo")
        (field (name "Comment") "STD_RES")
      )
      (libsource (lib "Altium_lib") (part "STD_RES"))
    )
    (comp (ref "R35")
      (value "100 Om")
      (footprint "RESC1608X50AN")
      (fields
        (field (name "MANUFACTURERPARTNUMBER") "RC0603FR-07100RL")
        (field (name "MANUFACTURER") "Yageo")
        (field (name "Comment") "STD_RES")
      )
      (libsource (lib "Altium_lib") (part "STD_RES"))
    )
    (comp (ref "R36")
      (value "1 kOm")
      (footprint "R0603")
      (fields
        (field (name "MANUFACTURERPARTNUMBER") "RC0603FR-071K00L")
        (field (name "MANUFACTURER") "Yageo")
        (field (name "Comment") "STD_RES")
      )
      (libsource (lib "") (part "STD_RES_1"))
    )
    (comp (ref "R37")
      (value "1 kOm")
      (footprint "R0603")
      (fields
        (field (name "MANUFACTURERPARTNUMBER") "RC0603FR-071K00L")
        (field (name "MANUFACTURER") "Yageo")
        (field (name "Comment") "STD_RES")
      )
      (libsource (lib "") (part "STD_RES_1"))
    )
    (comp (ref "R38")
      (value "1 kOm")
      (footprint "R0603")
      (fields
        (field (name "MANUFACTURERPARTNUMBER") "RC0603FR-071K00L")
        (field (name "MANUFACTURER") "Yageo")
        (field (name "Comment") "STD_RES")
      )
      (libsource (lib "") (part "STD_RES_1"))
    )
    (comp (ref "R39")
      (value "1 kOm")
      (footprint "R0603")
      (fields
        (field (name "MANUFACTURERPARTNUMBER") "RC0603FR-071K00L")
        (field (name "MANUFACTURER") "Yageo")
        (field (name "Comment") "STD_RES")
      )
      (libsource (lib "") (part "STD_RES_1"))
    )
    (comp (ref "R40")
      (value "1 kOm")
      (footprint "R0603")
      (fields
        (field (name "MANUFACTURERPARTNUMBER") "RC0603FR-071K00L")
        (field (name "MANUFACTURER") "Yageo")
        (field (name "Comment") "STD_RES")
      )
      (libsource (lib "") (part "STD_RES_1"))
    )
    (comp (ref "R41")
      (value "1 kOm")
      (footprint "R0603")
      (fields
        (field (name "MANUFACTURERPARTNUMBER") "RC0603FR-071K00L")
        (field (name "MANUFACTURER") "Yageo")
        (field (name "Comment") "STD_RES")
      )
      (libsource (lib "") (part "STD_RES_1"))
    )
    (comp (ref "R42")
      (value "1 kOm")
      (footprint "R0603")
      (fields
        (field (name "MANUFACTURERPARTNUMBER") "RC0603FR-071K00L")
        (field (name "MANUFACTURER") "Yageo")
        (field (name "Comment") "STD_RES")
      )
      (libsource (lib "") (part "STD_RES_1"))
    )
    (comp (ref "R43")
      (value "1 kOm")
      (footprint "R0603")
      (fields
        (field (name "MANUFACTURERPARTNUMBER") "RC0603FR-071K00L")
        (field (name "MANUFACTURER") "Yageo")
        (field (name "Comment") "STD_RES")
      )
      (libsource (lib "") (part "STD_RES_1"))
    )
    (comp (ref "R44")
      (value "1 kOm")
      (footprint "R0603")
      (fields
        (field (name "MANUFACTURERPARTNUMBER") "RC0603FR-071K00L")
        (field (name "MANUFACTURER") "Yageo")
        (field (name "Comment") "STD_RES")
      )
      (libsource (lib "") (part "STD_RES_1"))
    )
    (comp (ref "R45")
      (value "1 kOm")
      (footprint "R0603")
      (fields
        (field (name "MANUFACTURERPARTNUMBER") "RC0603FR-071K00L")
        (field (name "MANUFACTURER") "Yageo")
        (field (name "Comment") "STD_RES")
      )
      (libsource (lib "") (part "STD_RES_1"))
    )
    (comp (ref "R46")
      (value "1 kOm")
      (footprint "RESC1608X50AN")
      (fields
        (field (name "MANUFACTURERPARTNUMBER") "RC0603FR-071K00L")
        (field (name "MANUFACTURER") "Yageo")
        (field (name "Comment") "STD_RES")
      )
      (libsource (lib "") (part "STD_RES_2"))
    )
    (comp (ref "R47")
      (value "1 kOm")
      (footprint "RESC1608X50AN")
      (fields
        (field (name "MANUFACTURERPARTNUMBER") "RC0603FR-071K00L")
        (field (name "MANUFACTURER") "Yageo")
        (field (name "Comment") "STD_RES")
      )
      (libsource (lib "") (part "STD_RES_2"))
    )
    (comp (ref "R48")
      (value "1 kOm")
      (footprint "RESC1608X50AN")
      (fields
        (field (name "MANUFACTURERPARTNUMBER") "RC0603FR-071K00L")
        (field (name "MANUFACTURER") "Yageo")
        (field (name "Comment") "STD_RES")
      )
      (libsource (lib "") (part "STD_RES_2"))
    )
    (comp (ref "R49")
      (value "1 kOm")
      (footprint "RESC1608X50AN")
      (fields
        (field (name "MANUFACTURERPARTNUMBER") "RC0603FR-071K00L")
        (field (name "MANUFACTURER") "Yageo")
        (field (name "Comment") "STD_RES")
      )
      (libsource (lib "") (part "STD_RES_2"))
    )
    (comp (ref "R50")
      (value "1 kOm")
      (footprint "RESC1608X50AN")
      (fields
        (field (name "MANUFACTURERPARTNUMBER") "RC0603FR-071K00L")
        (field (name "MANUFACTURER") "Yageo")
        (field (name "Comment") "STD_RES")
      )
      (libsource (lib "") (part "STD_RES_2"))
    )
    (comp (ref "R51")
      (value "1.2 kOm")
      (footprint "RESC1608X50AN")
      (fields
        (field (name "MANUFACTURERPARTNUMBER") "RC0603JR-071K2L")
        (field (name "MANUFACTURER") "Yageo")
        (field (name "Comment") "STD_RES")
      )
      (libsource (lib "") (part "STD_RES_2"))
    )
    (comp (ref "R52")
      (value "7.5 kOm")
      (footprint "RESC1608X50AN")
      (fields
        (field (name "MANUFACTURERPARTNUMBER") "RC0603FR-077K50L")
        (field (name "MANUFACTURER") "Yageo")
        (field (name "Comment") "STD_RES")
      )
      (libsource (lib "") (part "STD_RES_2"))
    )
    (comp (ref "R53")
      (value "1 kOm")
      (footprint "RESC1608X50AN")
      (fields
        (field (name "MANUFACTURERPARTNUMBER") "RC0603FR-071K00L")
        (field (name "MANUFACTURER") "Yageo")
        (field (name "Comment") "STD_RES")
      )
      (libsource (lib "") (part "STD_RES_2"))
    )
    (comp (ref "R54")
      (value "100 Om")
      (footprint "RESC1608X50AN")
      (fields
        (field (name "MANUFACTURERPARTNUMBER") "RC0603FR-07100RL")
        (field (name "MANUFACTURER") "Yageo")
        (field (name "Comment") "STD_RES")
      )
      (libsource (lib "Altium_lib") (part "STD_RES"))
    )
    (comp (ref "R55")
      (value "1 kOm")
      (footprint "R0603")
      (fields
        (field (name "MANUFACTURERPARTNUMBER") "RC0603FR-071K00L")
        (field (name "MANUFACTURER") "Yageo")
        (field (name "Comment") "STD_RES")
      )
      (libsource (lib "") (part "STD_RES_1"))
    )
    (comp (ref "R56")
      (value "1 kOm")
      (footprint "R0603")
      (fields
        (field (name "MANUFACTURERPARTNUMBER") "RC0603FR-071K00L")
        (field (name "MANUFACTURER") "Yageo")
        (field (name "Comment") "STD_RES")
      )
      (libsource (lib "") (part "STD_RES_1"))
    )
    (comp (ref "R57")
      (value "1 kOm")
      (footprint "RESC1608X50AN")
      (fields
        (field (name "MANUFACTURERPARTNUMBER") "RC0603FR-071K00L")
        (field (name "MANUFACTURER") "Yageo")
        (field (name "Comment") "STD_RES")
      )
      (libsource (lib "") (part "STD_RES_2"))
    )
    (comp (ref "U1")
      (value "TP4056")
      (footprint "SOP127P600X175-9N")
      (description "Complete single cell Li-Ion battery with a constant current / constant voltage linear charger")
      (fields (field (name "MF") "NanJing Top Power ASIC Corp."))
      (libsource (lib "SCH_Wearing_sensor") (part "TP4056"))
    )
    (comp (ref "U2")
      (value "TP4056")
      (footprint "SOP127P600X175-9N")
      (description "Complete single cell Li-Ion battery with a constant current / constant voltage linear charger")
      (fields (field (name "MF") "NanJing Top Power ASIC Corp."))
      (libsource (lib "SCH_Wearing_sensor") (part "TP4056"))
    )
    (comp (ref "U3")
      (value "TP4056")
      (footprint "SOP127P600X175-9N")
      (description "Complete single cell Li-Ion battery with a constant current / constant voltage linear charger")
      (fields (field (name "MF") "NanJing Top Power ASIC Corp."))
      (libsource (lib "SCH_Wearing_sensor") (part "TP4056"))
    )
    (comp (ref "U4")
      (value "TP4056")
      (footprint "SOP127P600X175-9N")
      (description "Complete single cell Li-Ion battery with a constant current / constant voltage linear charger")
      (fields (field (name "MF") "NanJing Top Power ASIC Corp."))
      (libsource (lib "SCH_Wearing_sensor") (part "TP4056"))
    )
    (comp (ref "U5")
      (value "TP4056")
      (footprint "SOP127P600X175-9N")
      (description "Complete single cell Li-Ion battery with a constant current / constant voltage linear charger")
      (fields (field (name "MF") "NanJing Top Power ASIC Corp."))
      (libsource (lib "SCH_Wearing_sensor") (part "TP4056"))
    )
    (comp (ref "U6")
      (value "DW01A")
      (footprint "SOT23-6")
      (description "One Cell Lithium-ion/Polymer Battery Protection IC")
      (fields (field (name "MF") "Fortune Semiconductor"))
      (libsource (lib "SCH_Wearing_sensor") (part "DW01A"))
    )
    (comp (ref "U7")
      (value "DW01A")
      (footprint "SOT23-6")
      (description "One Cell Lithium-ion/Polymer Battery Protection IC")
      (fields (field (name "MF") "Fortune Semiconductor"))
      (libsource (lib "SCH_Wearing_sensor") (part "DW01A"))
    )
    (comp (ref "U8")
      (value "DW01A")
      (footprint "SOT23-6")
      (description "One Cell Lithium-ion/Polymer Battery Protection IC")
      (fields (field (name "MF") "Fortune Semiconductor"))
      (libsource (lib "SCH_Wearing_sensor") (part "DW01A"))
    )
    (comp (ref "U9")
      (value "DW01A")
      (footprint "SOT23-6")
      (description "One Cell Lithium-ion/Polymer Battery Protection IC")
      (fields (field (name "MF") "Fortune Semiconductor"))
      (libsource (lib "SCH_Wearing_sensor") (part "DW01A"))
    )
    (comp (ref "U10")
      (value "DW01A")
      (footprint "SOT23-6")
      (description "One Cell Lithium-ion/Polymer Battery Protection IC")
      (fields (field (name "MF") "Fortune Semiconductor"))
      (libsource (lib "SCH_Wearing_sensor") (part "DW01A"))
    )
    (comp (ref "U11")
      (value "TP4056")
      (footprint "SOP127P600X175-9N")
      (description "Complete single cell Li-Ion battery with a constant current / constant voltage linear charger")
      (fields (field (name "MF") "NanJing Top Power ASIC Corp."))
      (libsource (lib "SCH_Wearing_sensor") (part "TP4056"))
    )
    (comp (ref "U12")
      (value "TP4056")
      (footprint "SOP127P600X175-9N")
      (description "Complete single cell Li-Ion battery with a constant current / constant voltage linear charger")
      (fields (field (name "MF") "NanJing Top Power ASIC Corp."))
      (libsource (lib "SCH_Wearing_sensor") (part "TP4056"))
    )
    (comp (ref "U13")
      (value "TP4056")
      (footprint "SOP127P600X175-9N")
      (description "Complete single cell Li-Ion battery with a constant current / constant voltage linear charger")
      (fields (field (name "MF") "NanJing Top Power ASIC Corp."))
      (libsource (lib "SCH_Wearing_sensor") (part "TP4056"))
    )
    (comp (ref "U14")
      (value "TP4056")
      (footprint "SOP127P600X175-9N")
      (description "Complete single cell Li-Ion battery with a constant current / constant voltage linear charger")
      (fields (field (name "MF") "NanJing Top Power ASIC Corp."))
      (libsource (lib "SCH_Wearing_sensor") (part "TP4056"))
    )
    (comp (ref "U15")
      (value "TP4056")
      (footprint "SOP127P600X175-9N")
      (description "Complete single cell Li-Ion battery with a constant current / constant voltage linear charger")
      (fields (field (name "MF") "NanJing Top Power ASIC Corp."))
      (libsource (lib "SCH_Wearing_sensor") (part "TP4056"))
    )
    (comp (ref "U16")
      (value "DW01A")
      (footprint "SOT23-6")
      (description "One Cell Lithium-ion/Polymer Battery Protection IC")
      (fields (field (name "MF") "Fortune Semiconductor"))
      (libsource (lib "SCH_Wearing_sensor") (part "DW01A"))
    )
    (comp (ref "U17")
      (value "DW01A")
      (footprint "SOT23-6")
      (description "One Cell Lithium-ion/Polymer Battery Protection IC")
      (fields (field (name "MF") "Fortune Semiconductor"))
      (libsource (lib "SCH_Wearing_sensor") (part "DW01A"))
    )
    (comp (ref "U18")
      (value "DW01A")
      (footprint "SOT23-6")
      (description "One Cell Lithium-ion/Polymer Battery Protection IC")
      (fields (field (name "MF") "Fortune Semiconductor"))
      (libsource (lib "SCH_Wearing_sensor") (part "DW01A"))
    )
    (comp (ref "U19")
      (value "DW01A")
      (footprint "SOT23-6")
      (description "One Cell Lithium-ion/Polymer Battery Protection IC")
      (fields (field (name "MF") "Fortune Semiconductor"))
      (libsource (lib "SCH_Wearing_sensor") (part "DW01A"))
    )
    (comp (ref "U20")
      (value "DW01A")
      (footprint "SOT23-6")
      (description "One Cell Lithium-ion/Polymer Battery Protection IC")
      (fields (field (name "MF") "Fortune Semiconductor"))
      (libsource (lib "SCH_Wearing_sensor") (part "DW01A"))
    )
    (comp (ref "U21")
      (value "TP4056")
      (footprint "SOP127P600X175-9N")
      (description "Complete single cell Li-Ion battery with a constant current / constant voltage linear charger")
      (fields (field (name "MF") "NanJing Top Power ASIC Corp."))
      (libsource (lib "SCH_Wearing_sensor") (part "TP4056"))
    )
    (comp (ref "U22")
      (value "MT3608")
      (footprint "SOT95P280X145-6N")
      (description "High Efficiency 1.2MHz2A Step Up Converter")
      (fields (field (name "MF") "Aerosemi Technology Co., Ltd"))
      (libsource (lib "SCH_Wearing_sensor") (part "MT3608"))
    )
    (comp (ref "U23")
      (value "DW01A")
      (footprint "SOT23-6")
      (description "One Cell Lithium-ion/Polymer Battery Protection IC")
      (fields (field (name "MF") "Fortune Semiconductor"))
      (libsource (lib "SCH_Wearing_sensor") (part "DW01A"))
    )
    (comp (ref "U24")
      (value "ESP32-DEVKITC-32D")
      (footprint "MODULE_ESP32-DEVKITC-32D")
      (description "WiFi Development Tools (802.11) ESP32 General Development Kit, ESP32-WROOM-32D on the board")
      (fields (field (name "MF") "Espressif Systems"))
      (libsource (lib "SCH_Wearing_sensor") (part "ESP32-DEVKITC-32D"))
    )
    (comp (ref "X1")
      (value "Charge Connector")
      (footprint "POGO PINS")
      (description "Выводы под плату зарядки")
      (libsource (lib "SCH_Wearing_sensor") (part "Charge Connector"))
    )
    (comp (ref "X2")
      (value "Charge Connector")
      (footprint "POGO PINS")
      (description "Выводы под плату зарядки")
      (libsource (lib "SCH_Wearing_sensor") (part "Charge Connector"))
    )
    (comp (ref "X3")
      (value "Charge Connector")
      (footprint "POGO PINS")
      (description "Выводы под плату зарядки")
      (libsource (lib "SCH_Wearing_sensor") (part "Charge Connector"))
    )
    (comp (ref "X4")
      (value "Charge Connector")
      (footprint "POGO PINS")
      (description "Выводы под плату зарядки")
      (libsource (lib "SCH_Wearing_sensor") (part "Charge Connector"))
    )
    (comp (ref "X5")
      (value "Charge Connector")
      (footprint "POGO PINS")
      (description "Выводы под плату зарядки")
      (libsource (lib "SCH_Wearing_sensor") (part "Charge Connector"))
    )
    (comp (ref "X6")
      (value "Charge Connector")
      (footprint "POGO PINS")
      (description "Выводы под плату зарядки")
      (libsource (lib "SCH_Wearing_sensor") (part "Charge Connector"))
    )
    (comp (ref "X7")
      (value "Charge Connector")
      (footprint "POGO PINS")
      (description "Выводы под плату зарядки")
      (libsource (lib "SCH_Wearing_sensor") (part "Charge Connector"))
    )
    (comp (ref "X8")
      (value "Charge Connector")
      (footprint "POGO PINS")
      (description "Выводы под плату зарядки")
      (libsource (lib "SCH_Wearing_sensor") (part "Charge Connector"))
    )
    (comp (ref "X9")
      (value "Charge Connector")
      (footprint "POGO PINS")
      (description "Выводы под плату зарядки")
      (libsource (lib "SCH_Wearing_sensor") (part "Charge Connector"))
    )
    (comp (ref "X10")
      (value "Charge Connector")
      (footprint "POGO PINS")
      (description "Выводы под плату зарядки")
      (libsource (lib "SCH_Wearing_sensor") (part "Charge Connector"))
    )
    (comp (ref "X11")
      (value "CON2")
      (footprint "CON4_bat")
      (description "Коннектор двухконтактный")
      (fields (field (name "MANUFACTURERPARTNUMBER") "LP401230") (field (name "MANUFACTURER") "Robiton"))
      (libsource (lib "SCH_Wearing_sensor") (part "CON2"))
    )
    (comp (ref "X12")
      (value "CON2")
      (footprint "CON4_bat")
      (description "Коннектор двухконтактный")
      (fields (field (name "MANUFACTURERPARTNUMBER") "LP401230") (field (name "MANUFACTURER") "Robiton"))
      (libsource (lib "SCH_Wearing_sensor") (part "CON2"))
    )
    (comp (ref "X13")
      (value "CON2")
      (footprint "CON4_bat")
      (description "Коннектор двухконтактный")
      (fields (field (name "MANUFACTURERPARTNUMBER") "LP401230") (field (name "MANUFACTURER") "Robiton"))
      (libsource (lib "SCH_Wearing_sensor") (part "CON2"))
    )
  )
  (nets
    (net (code "1") (name "/CHRG_1") (class "Default")
      (node (ref "R12") (pin "1") (pinfunction "1_1") (pintype "passive"))
      (node (ref "U1") (pin "7") (pinfunction "~{CHRG}_7") (pintype "output"))
    )
    (net (code "2") (name "/CHRG_2") (class "Default")
      (node (ref "R14") (pin "1") (pinfunction "1_1") (pintype "passive"))
      (node (ref "U2") (pin "7") (pinfunction "~{CHRG}_7") (pintype "output"))
    )
    (net (code "3") (name "/CHRG_3") (class "Default")
      (node (ref "R16") (pin "1") (pinfunction "1_1") (pintype "passive"))
      (node (ref "U3") (pin "7") (pinfunction "~{CHRG}_7") (pintype "output"))
    )
    (net (code "4") (name "/CHRG_4") (class "Default")
      (node (ref "R18") (pin "1") (pinfunction "1_1") (pintype "passive"))
      (node (ref "U4") (pin "7") (pinfunction "~{CHRG}_7") (pintype "output"))
    )
    (net (code "5") (name "/CHRG_5") (class "Default")
      (node (ref "R20") (pin "1") (pinfunction "1_1") (pintype "passive"))
      (node (ref "U5") (pin "7") (pinfunction "~{CHRG}_7") (pintype "output"))
    )
    (net (code "6") (name "/CHRG_6") (class "Default")
      (node (ref "R37") (pin "1") (pinfunction "1_1") (pintype "passive"))
      (node (ref "U11") (pin "7") (pinfunction "~{CHRG}_7") (pintype "output"))
    )
    (net (code "7") (name "/CHRG_7") (class "Default")
      (node (ref "R39") (pin "1") (pinfunction "1_1") (pintype "passive"))
      (node (ref "U12") (pin "7") (pinfunction "~{CHRG}_7") (pintype "output"))
    )
    (net (code "8") (name "/CHRG_8") (class "Default")
      (node (ref "R41") (pin "1") (pinfunction "1_1") (pintype "passive"))
      (node (ref "U13") (pin "7") (pinfunction "~{CHRG}_7") (pintype "output"))
    )
    (net (code "9") (name "/CHRG_9") (class "Default")
      (node (ref "R43") (pin "1") (pinfunction "1_1") (pintype "passive"))
      (node (ref "U14") (pin "7") (pinfunction "~{CHRG}_7") (pintype "output"))
    )
    (net (code "10") (name "/CHRG_10") (class "Default")
      (node (ref "R45") (pin "1") (pinfunction "1_1") (pintype "passive"))
      (node (ref "U15") (pin "7") (pinfunction "~{CHRG}_7") (pintype "output"))
    )
    (net (code "11") (name "/CHRG_M") (class "Default")
      (node (ref "R56") (pin "1") (pinfunction "1_1") (pintype "passive"))
      (node (ref "U21") (pin "7") (pinfunction "~{CHRG}_7") (pintype "output"))
    )
    (net (code "12") (name "/STDBY_1") (class "Default")
      (node (ref "R11") (pin "1") (pinfunction "1_1") (pintype "passive"))
      (node (ref "U1") (pin "6") (pinfunction "~{STDBY}_6") (pintype "output"))
    )
    (net (code "13") (name "/STDBY_2") (class "Default")
      (node (ref "R13") (pin "1") (pinfunction "1_1") (pintype "passive"))
      (node (ref "U2") (pin "6") (pinfunction "~{STDBY}_6") (pintype "output"))
    )
    (net (code "14") (name "/STDBY_3") (class "Default")
      (node (ref "R15") (pin "1") (pinfunction "1_1") (pintype "passive"))
      (node (ref "U3") (pin "6") (pinfunction "~{STDBY}_6") (pintype "output"))
    )
    (net (code "15") (name "/STDBY_4") (class "Default")
      (node (ref "R17") (pin "1") (pinfunction "1_1") (pintype "passive"))
      (node (ref "U4") (pin "6") (pinfunction "~{STDBY}_6") (pintype "output"))
    )
    (net (code "16") (name "/STDBY_5") (class "Default")
      (node (ref "R19") (pin "1") (pinfunction "1_1") (pintype "passive"))
      (node (ref "U5") (pin "6") (pinfunction "~{STDBY}_6") (pintype "output"))
    )
    (net (code "17") (name "/STDBY_6") (class "Default")
      (node (ref "R36") (pin "1") (pinfunction "1_1") (pintype "passive"))
      (node (ref "U11") (pin "6") (pinfunction "~{STDBY}_6") (pintype "output"))
    )
    (net (code "18") (name "/STDBY_7") (class "Default")
      (node (ref "R38") (pin "1") (pinfunction "1_1") (pintype "passive"))
      (node (ref "U12") (pin "6") (pinfunction "~{STDBY}_6") (pintype "output"))
    )
    (net (code "19") (name "/STDBY_8") (class "Default")
      (node (ref "R40") (pin "1") (pinfunction "1_1") (pintype "passive"))
      (node (ref "U13") (pin "6") (pinfunction "~{STDBY}_6") (pintype "output"))
    )
    (net (code "20") (name "/STDBY_9") (class "Default")
      (node (ref "R42") (pin "1") (pinfunction "1_1") (pintype "passive"))
      (node (ref "U14") (pin "6") (pinfunction "~{STDBY}_6") (pintype "output"))
    )
    (net (code "21") (name "/STDBY_10") (class "Default")
      (node (ref "R44") (pin "1") (pinfunction "1_1") (pintype "passive"))
      (node (ref "U15") (pin "6") (pinfunction "~{STDBY}_6") (pintype "output"))
    )
    (net (code "22") (name "/STDBY_M") (class "Default")
      (node (ref "R55") (pin "1") (pinfunction "1_1") (pintype "passive"))
      (node (ref "U21") (pin "6") (pinfunction "~{STDBY}_6") (pintype "output"))
    )
    (net (code "23") (name "5V") (class "Default")
      (node (ref "C1") (pin "2") (pinfunction "2_2") (pintype "passive"))
      (node (ref "C16") (pin "2") (pinfunction "2_2") (pintype "passive"))
      (node (ref "C17") (pin "2") (pinfunction "2_2") (pintype "passive"))
      (node (ref "C18") (pin "2") (pinfunction "2_2") (pintype "passive"))
      (node (ref "C19") (pin "2") (pinfunction "2_2") (pintype "passive"))
      (node (ref "C2") (pin "2") (pinfunction "2_2") (pintype "passive"))
      (node (ref "C20") (pin "2") (pinfunction "2_2") (pintype "passive"))
      (node (ref "C3") (pin "2") (pinfunction "2_2") (pintype "passive"))
      (node (ref "C34") (pin "2") (pinfunction "2_2") (pintype "passive"))
      (node (ref "C4") (pin "2") (pinfunction "2_2") (pintype "passive"))
      (node (ref "C5") (pin "2") (pinfunction "2_2") (pintype "passive"))
      (node (ref "D1") (pin "A") (pinfunction "A_A") (pintype "passive"))
      (node (ref "D10") (pin "A") (pinfunction "A_A") (pintype "passive"))
      (node (ref "D11") (pin "A") (pinfunction "A_A") (pintype "passive"))
      (node (ref "D12") (pin "A") (pinfunction "A_A") (pintype "passive"))
      (node (ref "D13") (pin "A") (pinfunction "A_A") (pintype "passive"))
      (node (ref "D14") (pin "A") (pinfunction "A_A") (pintype "passive"))
      (node (ref "D15") (pin "A") (pinfunction "A_A") (pintype "passive"))
      (node (ref "D16") (pin "A") (pinfunction "A_A") (pintype "passive"))
      (node (ref "D17") (pin "A") (pinfunction "A_A") (pintype "passive"))
      (node (ref "D18") (pin "A") (pinfunction "A_A") (pintype "passive"))
      (node (ref "D19") (pin "A") (pinfunction "A_A") (pintype "passive"))
      (node (ref "D2") (pin "A") (pinfunction "A_A") (pintype "passive"))
      (node (ref "D20") (pin "A") (pinfunction "A_A") (pintype "passive"))
      (node (ref "D21") (pin "1") (pinfunction "K_1") (pintype "passive"))
      (node (ref "D23") (pin "A") (pinfunction "A_A") (pintype "passive"))
      (node (ref "D24") (pin "A") (pinfunction "A_A") (pintype "passive"))
      (node (ref "D3") (pin "A") (pinfunction "A_A") (pintype "passive"))
      (node (ref "D4") (pin "A") (pinfunction "A_A") (pintype "passive"))
      (node (ref "D5") (pin "A") (pinfunction "A_A") (pintype "passive"))
      (node (ref "D6") (pin "A") (pinfunction "A_A") (pintype "passive"))
      (node (ref "D7") (pin "A") (pinfunction "A_A") (pintype "passive"))
      (node (ref "D8") (pin "A") (pinfunction "A_A") (pintype "passive"))
      (node (ref "D9") (pin "A") (pinfunction "A_A") (pintype "passive"))
      (node (ref "R52") (pin "2") (pinfunction "2_2") (pintype "passive"))
      (node (ref "U1") (pin "4") (pinfunction "VCC_4") (pintype "power_in"))
      (node (ref "U1") (pin "8") (pinfunction "CE_8") (pintype "input"))
      (node (ref "U11") (pin "4") (pinfunction "VCC_4") (pintype "power_in"))
      (node (ref "U11") (pin "8") (pinfunction "CE_8") (pintype "input"))
      (node (ref "U12") (pin "4") (pinfunction "VCC_4") (pintype "power_in"))
      (node (ref "U12") (pin "8") (pinfunction "CE_8") (pintype "input"))
      (node (ref "U13") (pin "4") (pinfunction "VCC_4") (pintype "power_in"))
      (node (ref "U13") (pin "8") (pinfunction "CE_8") (pintype "input"))
      (node (ref "U14") (pin "4") (pinfunction "VCC_4") (pintype "power_in"))
      (node (ref "U14") (pin "8") (pinfunction "CE_8") (pintype "input"))
      (node (ref "U15") (pin "4") (pinfunction "VCC_4") (pintype "power_in"))
      (node (ref "U15") (pin "8") (pinfunction "CE_8") (pintype "input"))
      (node (ref "U2") (pin "4") (pinfunction "VCC_4") (pintype "power_in"))
      (node (ref "U2") (pin "8") (pinfunction "CE_8") (pintype "input"))
      (node (ref "U24") (pin "J2-19") (pinfunction "EXT_5V_J2-19") (pintype "power_in"))
      (node (ref "U3") (pin "4") (pinfunction "VCC_4") (pintype "power_in"))
      (node (ref "U3") (pin "8") (pinfunction "CE_8") (pintype "input"))
      (node (ref "U4") (pin "4") (pinfunction "VCC_4") (pintype "power_in"))
      (node (ref "U4") (pin "8") (pinfunction "CE_8") (pintype "input"))
      (node (ref "U5") (pin "4") (pinfunction "VCC_4") (pintype "power_in"))
      (node (ref "U5") (pin "8") (pinfunction "CE_8") (pintype "input"))
    )
    (net (code "24") (name "BAT_GND_MAIN") (class "Default")
      (node (ref "C35") (pin "1") (pinfunction "1_1") (pintype "passive"))
      (node (ref "Q11") (pin "6") (pinfunction "S2_6") (pintype "passive"))
      (node (ref "Q11") (pin "7") (pinfunction "S2_7") (pintype "passive"))
      (node (ref "U23") (pin "6") (pinfunction "GND_6") (pintype "power_in"))
      (node (ref "X13") (pin "2") (pintype "passive"))
    )
    (net (code "25") (name "BAT_GND_WS1") (class "Default")
      (node (ref "C13") (pin "1") (pinfunction "1_1") (pintype "passive"))
      (node (ref "Q1") (pin "6") (pinfunction "S2_6") (pintype "passive"))
      (node (ref "Q1") (pin "7") (pinfunction "S2_7") (pintype "passive"))
      (node (ref "U6") (pin "6") (pinfunction "GND_6") (pintype "power_in"))
      (node (ref "X1") (pin "3") (pintype "passive"))
    )
    (net (code "26") (name "BAT_GND_WS2") (class "Default")
      (node (ref "C14") (pin "1") (pinfunction "1_1") (pintype "passive"))
      (node (ref "Q2") (pin "6") (pinfunction "S2_6") (pintype "passive"))
      (node (ref "Q2") (pin "7") (pinfunction "S2_7") (pintype "passive"))
      (node (ref "U7") (pin "6") (pinfunction "GND_6") (pintype "power_in"))
      (node (ref "X2") (pin "3") (pintype "passive"))
    )
    (net (code "27") (name "BAT_GND_WS3") (class "Default")
      (node (ref "C15") (pin "1") (pinfunction "1_1") (pintype "passive"))
      (node (ref "Q3") (pin "6") (pinfunction "S2_6") (pintype "passive"))
      (node (ref "Q3") (pin "7") (pinfunction "S2_7") (pintype "passive"))
      (node (ref "U8") (pin "6") (pinfunction "GND_6") (pintype "power_in"))
      (node (ref "X3") (pin "3") (pintype "passive"))
    )
    (net (code "28") (name "BAT_GND_WS4") (class "Default")
      (node (ref "C11") (pin "1") (pinfunction "1_1") (pintype "passive"))
      (node (ref "Q4") (pin "6") (pinfunction "S2_6") (pintype "passive"))
      (node (ref "Q4") (pin "7") (pinfunction "S2_7") (pintype "passive"))
      (node (ref "U9") (pin "6") (pinfunction "GND_6") (pintype "power_in"))
      (node (ref "X4") (pin "3") (pintype "passive"))
    )
    (net (code "29") (name "BAT_GND_WS5") (class "Default")
      (node (ref "C12") (pin "1") (pinfunction "1_1") (pintype "passive"))
      (node (ref "Q5") (pin "6") (pinfunction "S2_6") (pintype "passive"))
      (node (ref "Q5") (pin "7") (pinfunction "S2_7") (pintype "passive"))
      (node (ref "U10") (pin "6") (pinfunction "GND_6") (pintype "power_in"))
      (node (ref "X5") (pin "3") (pintype "passive"))
    )
    (net (code "30") (name "BAT_GND_WS6") (class "Default")
      (node (ref "C26") (pin "1") (pinfunction "1_1") (pintype "passive"))
      (node (ref "Q6") (pin "6") (pinfunction "S2_6") (pintype "passive"))
      (node (ref "Q6") (pin "7") (pinfunction "S2_7") (pintype "passive"))
      (node (ref "U16") (pin "6") (pinfunction "GND_6") (pintype "power_in"))
      (node (ref "X6") (pin "3") (pintype "passive"))
    )
    (net (code "31") (name "BAT_GND_WS7") (class "Default")
      (node (ref "C27") (pin "1") (pinfunction "1_1") (pintype "passive"))
      (node (ref "Q7") (pin "6") (pinfunction "S2_6") (pintype "passive"))
      (node (ref "Q7") (pin "7") (pinfunction "S2_7") (pintype "passive"))
      (node (ref "U17") (pin "6") (pinfunction "GND_6") (pintype "power_in"))
      (node (ref "X7") (pin "3") (pintype "passive"))
    )
    (net (code "32") (name "BAT_GND_WS8") (class "Default")
      (node (ref "C28") (pin "1") (pinfunction "1_1") (pintype "passive"))
      (node (ref "Q8") (pin "6") (pinfunction "S2_6") (pintype "passive"))
      (node (ref "Q8") (pin "7") (pinfunction "S2_7") (pintype "passive"))
      (node (ref "U18") (pin "6") (pinfunction "GND_6") (pintype "power_in"))
      (node (ref "X8") (pin "3") (pintype "passive"))
    )
    (net (code "33") (name "BAT_GND_WS9") (class "Default")
      (node (ref "C29") (pin "1") (pinfunction "1_1") (pintype "passive"))
      (node (ref "Q9") (pin "6") (pinfunction "S2_6") (pintype "passive"))
      (node (ref "Q9") (pin "7") (pinfunction "S2_7") (pintype "passive"))
      (node (ref "U19") (pin "6") (pinfunction "GND_6") (pintype "power_in"))
      (node (ref "X9") (pin "3") (pintype "passive"))
    )
    (net (code "34") (name "BAT_GND_WS10") (class "Default")
      (node (ref "C30") (pin "1") (pinfunction "1_1") (pintype "passive"))
      (node (ref "Q10") (pin "6") (pinfunction "S2_6") (pintype "passive"))
      (node (ref "Q10") (pin "7") (pinfunction "S2_7") (pintype "passive"))
      (node (ref "U20") (pin "6") (pinfunction "GND_6") (pintype "power_in"))
      (node (ref "X10") (pin "3") (pintype "passive"))
    )
    (net (code "35") (name "BAT_MAIN") (class "Default")
      (node (ref "C33") (pin "2") (pinfunction "2_2") (pintype "passive"))
      (node (ref "D22") (pin "2") (pinfunction "A_2") (pintype "passive"))
      (node (ref "R54") (pin "2") (pinfunction "2_2") (pintype "passive"))
      (node (ref "U21") (pin "5") (pinfunction "BAT_5") (pintype "output"))
      (node (ref "X13") (pin "1") (pintype "passive"))
    )
    (net (code "36") (name "Charge_Bat_WS_1") (class "Default")
      (node (ref "C9") (pin "2") (pinfunction "2_2") (pintype "passive"))
      (node (ref "R9") (pin "2") (pinfunction "2_2") (pintype "passive"))
      (node (ref "U1") (pin "5") (pinfunction "BAT_5") (pintype "output"))
      (node (ref "X1") (pin "1") (pintype "passive"))
      (node (ref "X1") (pin "2") (pintype "passive"))
    )
    (net (code "37") (name "Charge_Bat_WS_2") (class "Default")
      (node (ref "C10") (pin "2") (pinfunction "2_2") (pintype "passive"))
      (node (ref "R10") (pin "2") (pinfunction "2_2") (pintype "passive"))
      (node (ref "U2") (pin "5") (pinfunction "BAT_5") (pintype "output"))
      (node (ref "X2") (pin "1") (pintype "passive"))
      (node (ref "X2") (pin "2") (pintype "passive"))
    )
    (net (code "38") (name "Charge_Bat_WS_3") (class "Default")
      (node (ref "C6") (pin "2") (pinfunction "2_2") (pintype "passive"))
      (node (ref "R6") (pin "2") (pinfunction "2_2") (pintype "passive"))
      (node (ref "U3") (pin "5") (pinfunction "BAT_5") (pintype "output"))
      (node (ref "X3") (pin "1") (pintype "passive"))
      (node (ref "X3") (pin "2") (pintype "passive"))
    )
    (net (code "39") (name "Charge_Bat_WS_4") (class "Default")
      (node (ref "C7") (pin "2") (pinfunction "2_2") (pintype "passive"))
      (node (ref "R7") (pin "2") (pinfunction "2_2") (pintype "passive"))
      (node (ref "U4") (pin "5") (pinfunction "BAT_5") (pintype "output"))
      (node (ref "X4") (pin "1") (pintype "passive"))
      (node (ref "X4") (pin "2") (pintype "passive"))
    )
    (net (code "40") (name "Charge_Bat_WS_5") (class "Default")
      (node (ref "C8") (pin "2") (pinfunction "2_2") (pintype "passive"))
      (node (ref "R8") (pin "2") (pinfunction "2_2") (pintype "passive"))
      (node (ref "U5") (pin "5") (pinfunction "BAT_5") (pintype "output"))
      (node (ref "X5") (pin "1") (pintype "passive"))
      (node (ref "X5") (pin "2") (pintype "passive"))
    )
    (net (code "41") (name "Charge_Bat_WS_6") (class "Default")
      (node (ref "C21") (pin "2") (pinfunction "2_2") (pintype "passive"))
      (node (ref "R31") (pin "2") (pinfunction "2_2") (pintype "passive"))
      (node (ref "U11") (pin "5") (pinfunction "BAT_5") (pintype "output"))
      (node (ref "X6") (pin "1") (pintype "passive"))
      (node (ref "X6") (pin "2") (pintype "passive"))
    )
    (net (code "42") (name "Charge_Bat_WS_7") (class "Default")
      (node (ref "C22") (pin "2") (pinfunction "2_2") (pintype "passive"))
      (node (ref "R32") (pin "2") (pinfunction "2_2") (pintype "passive"))
      (node (ref "U12") (pin "5") (pinfunction "BAT_5") (pintype "output"))
      (node (ref "X7") (pin "1") (pintype "passive"))
      (node (ref "X7") (pin "2") (pintype "passive"))
    )
    (net (code "43") (name "Charge_Bat_WS_8") (class "Default")
      (node (ref "C23") (pin "2") (pinfunction "2_2") (pintype "passive"))
      (node (ref "R33") (pin "2") (pinfunction "2_2") (pintype "passive"))
      (node (ref "U13") (pin "5") (pinfunction "BAT_5") (pintype "output"))
      (node (ref "X8") (pin "1") (pintype "passive"))
      (node (ref "X8") (pin "2") (pintype "passive"))
    )
    (net (code "44") (name "Charge_Bat_WS_9") (class "Default")
      (node (ref "C24") (pin "2") (pinfunction "2_2") (pintype "passive"))
      (node (ref "R34") (pin "2") (pinfunction "2_2") (pintype "passive"))
      (node (ref "U14") (pin "5") (pinfunction "BAT_5") (pintype "output"))
      (node (ref "X9") (pin "1") (pintype "passive"))
      (node (ref "X9") (pin "2") (pintype "passive"))
    )
    (net (code "45") (name "Charge_Bat_WS_10") (class "Default")
      (node (ref "C25") (pin "2") (pinfunction "2_2") (pintype "passive"))
      (node (ref "R35") (pin "2") (pinfunction "2_2") (pintype "passive"))
      (node (ref "U15") (pin "5") (pinfunction "BAT_5") (pintype "output"))
      (node (ref "X10") (pin "1") (pintype "passive"))
      (node (ref "X10") (pin "2") (pintype "passive"))
    )
    (net (code "46") (name "GND") (class "Default")
      (node (ref "C1") (pin "1") (pinfunction "1_1") (pintype "passive"))
      (node (ref "C10") (pin "1") (pinfunction "1_1") (pintype "passive"))
      (node (ref "C16") (pin "1") (pinfunction "1_1") (pintype "passive"))
      (node (ref "C17") (pin "1") (pinfunction "1_1") (pintype "passive"))
      (node (ref "C18") (pin "1") (pinfunction "1_1") (pintype "passive"))
      (node (ref "C19") (pin "1") (pinfunction "1_1") (pintype "passive"))
      (node (ref "C2") (pin "1") (pinfunction "1_1") (pintype "passive"))
      (node (ref "C20") (pin "1") (pinfunction "1_1") (pintype "passive"))
      (node (ref "C21") (pin "1") (pinfunction "1_1") (pintype "passive"))
      (node (ref "C22") (pin "1") (pinfunction "1_1") (pintype "passive"))
      (node (ref "C23") (pin "1") (pinfunction "1_1") (pintype "passive"))
      (node (ref "C24") (pin "1") (pinfunction "1_1") (pintype "passive"))
      (node (ref "C25") (pin "1") (pinfunction "1_1") (pintype "passive"))
      (node (ref "C3") (pin "1") (pinfunction "1_1") (pintype "passive"))
      (node (ref "C31") (pin "1") (pinfunction "1_1") (pintype "passive"))
      (node (ref "C32") (pin "1") (pinfunction "1_1") (pintype "passive"))
      (node (ref "C33") (pin "1") (pinfunction "1_1") (pintype "passive"))
      (node (ref "C34") (pin "1") (pinfunction "1_1") (pintype "passive"))
      (node (ref "C4") (pin "1") (pinfunction "1_1") (pintype "passive"))
      (node (ref "C5") (pin "1") (pinfunction "1_1") (pintype "passive"))
      (node (ref "C6") (pin "1") (pinfunction "1_1") (pintype "passive"))
      (node (ref "C7") (pin "1") (pinfunction "1_1") (pintype "passive"))
      (node (ref "C8") (pin "1") (pinfunction "1_1") (pintype "passive"))
      (node (ref "C9") (pin "1") (pinfunction "1_1") (pintype "passive"))
      (node (ref "Q1") (pin "2") (pinfunction "S1_2") (pintype "passive"))
      (node (ref "Q1") (pin "3") (pinfunction "S1_3") (pintype "passive"))
      (node (ref "Q10") (pin "2") (pinfunction "S1_2") (pintype "passive"))
      (node (ref "Q10") (pin "3") (pinfunction "S1_3") (pintype "passive"))
      (node (ref "Q11") (pin "2") (pinfunction "S1_2") (pintype "passive"))
      (node (ref "Q11") (pin "3") (pinfunction "S1_3") (pintype "passive"))
      (node (ref "Q2") (pin "2") (pinfunction "S1_2") (pintype "passive"))
      (node (ref "Q2") (pin "3") (pinfunction "S1_3") (pintype "passive"))
      (node (ref "Q3") (pin "2") (pinfunction "S1_2") (pintype "passive"))
      (node (ref "Q3") (pin "3") (pinfunction "S1_3") (pintype "passive"))
      (node (ref "Q4") (pin "2") (pinfunction "S1_2") (pintype "passive"))
      (node (ref "Q4") (pin "3") (pinfunction "S1_3") (pintype "passive"))
      (node (ref "Q5") (pin "2") (pinfunction "S1_2") (pintype "passive"))
      (node (ref "Q5") (pin "3") (pinfunction "S1_3") (pintype "passive"))
      (node (ref "Q6") (pin "2") (pinfunction "S1_2") (pintype "passive"))
      (node (ref "Q6") (pin "3") (pinfunction "S1_3") (pintype "passive"))
      (node (ref "Q7") (pin "2") (pinfunction "S1_2") (pintype "passive"))
      (node (ref "Q7") (pin "3") (pinfunction "S1_3") (pintype "passive"))
      (node (ref "Q8") (pin "2") (pinfunction "S1_2") (pintype "passive"))
      (node (ref "Q8") (pin "3") (pinfunction "S1_3") (pintype "passive"))
      (node (ref "Q9") (pin "2") (pinfunction "S1_2") (pintype "passive"))
      (node (ref "Q9") (pin "3") (pinfunction "S1_3") (pintype "passive"))
      (node (ref "R1") (pin "1") (pinfunction "1_1") (pintype "passive"))
      (node (ref "R2") (pin "1") (pinfunction "1_1") (pintype "passive"))
      (node (ref "R21") (pin "1") (pinfunction "1_1") (pintype "passive"))
      (node (ref "R22") (pin "1") (pinfunction "1_1") (pintype "passive"))
      (node (ref "R23") (pin "1") (pinfunction "1_1") (pintype "passive"))
      (node (ref "R24") (pin "1") (pinfunction "1_1") (pintype "passive"))
      (node (ref "R25") (pin "1") (pinfunction "1_1") (pintype "passive"))
      (node (ref "R26") (pin "1") (pinfunction "1_1") (pintype "passive"))
      (node (ref "R27") (pin "1") (pinfunction "1_1") (pintype "passive"))
      (node (ref "R28") (pin "1") (pinfunction "1_1") (pintype "passive"))
      (node (ref "R29") (pin "1") (pinfunction "1_1") (pintype "passive"))
      (node (ref "R3") (pin "1") (pinfunction "1_1") (pintype "passive"))
      (node (ref "R30") (pin "1") (pinfunction "1_1") (pintype "passive"))
      (node (ref "R4") (pin "1") (pinfunction "1_1") (pintype "passive"))
      (node (ref "R46") (pin "1") (pinfunction "1_1") (pintype "passive"))
      (node (ref "R47") (pin "1") (pinfunction "1_1") (pintype "passive"))
      (node (ref "R48") (pin "1") (pinfunction "1_1") (pintype "passive"))
      (node (ref "R49") (pin "1") (pinfunction "1_1") (pintype "passive"))
      (node (ref "R5") (pin "1") (pinfunction "1_1") (pintype "passive"))
      (node (ref "R50") (pin "1") (pinfunction "1_1") (pintype "passive"))
      (node (ref "R51") (pin "1") (pinfunction "1_1") (pintype "passive"))
      (node (ref "R53") (pin "1") (pinfunction "1_1") (pintype "passive"))
      (node (ref "R57") (pin "1") (pinfunction "1_1") (pintype "passive"))
      (node (ref "U1") (pin "1") (pinfunction "TEMP_1") (pintype "input"))
      (node (ref "U1") (pin "3") (pinfunction "GND_3") (pintype "power_in"))
      (node (ref "U1") (pin "9") (pinfunction "EP_9") (pintype "passive"))
      (node (ref "U11") (pin "1") (pinfunction "TEMP_1") (pintype "input"))
      (node (ref "U11") (pin "3") (pinfunction "GND_3") (pintype "power_in"))
      (node (ref "U11") (pin "9") (pinfunction "EP_9") (pintype "passive"))
      (node (ref "U12") (pin "1") (pinfunction "TEMP_1") (pintype "input"))
      (node (ref "U12") (pin "3") (pinfunction "GND_3") (pintype "power_in"))
      (node (ref "U12") (pin "9") (pinfunction "EP_9") (pintype "passive"))
      (node (ref "U13") (pin "1") (pinfunction "TEMP_1") (pintype "input"))
      (node (ref "U13") (pin "3") (pinfunction "GND_3") (pintype "power_in"))
      (node (ref "U13") (pin "9") (pinfunction "EP_9") (pintype "passive"))
      (node (ref "U14") (pin "1") (pinfunction "TEMP_1") (pintype "input"))
      (node (ref "U14") (pin "3") (pinfunction "GND_3") (pintype "power_in"))
      (node (ref "U14") (pin "9") (pinfunction "EP_9") (pintype "passive"))
      (node (ref "U15") (pin "1") (pinfunction "TEMP_1") (pintype "input"))
      (node (ref "U15") (pin "3") (pinfunction "GND_3") (pintype "power_in"))
      (node (ref "U15") (pin "9") (pinfunction "EP_9") (pintype "passive"))
      (node (ref "U2") (pin "1") (pinfunction "TEMP_1") (pintype "input"))
      (node (ref "U2") (pin "3") (pinfunction "GND_3") (pintype "power_in"))
      (node (ref "U2") (pin "9") (pinfunction "EP_9") (pintype "passive"))
      (node (ref "U21") (pin "1") (pinfunction "TEMP_1") (pintype "input"))
      (node (ref "U21") (pin "3") (pinfunction "GND_3") (pintype "power_in"))
      (node (ref "U21") (pin "9") (pinfunction "EP_9") (pintype "passive"))
      (node (ref "U22") (pin "2") (pinfunction "GND_2") (pintype "power_in"))
      (node (ref "U24") (pin "J2-14") (pinfunction "GND1_J2-14") (pintype "power_in"))
      (node (ref "U24") (pin "J3-1") (pinfunction "GND3_J3-1") (pintype "power_in"))
      (node (ref "U24") (pin "J3-7") (pinfunction "GND2_J3-7") (pintype "power_in"))
      (node (ref "U3") (pin "1") (pinfunction "TEMP_1") (pintype "input"))
      (node (ref "U3") (pin "3") (pinfunction "GND_3") (pintype "power_in"))
      (node (ref "U3") (pin "9") (pinfunction "EP_9") (pintype "passive"))
      (node (ref "U4") (pin "1") (pinfunction "TEMP_1") (pintype "input"))
      (node (ref "U4") (pin "3") (pinfunction "GND_3") (pintype "power_in"))
      (node (ref "U4") (pin "9") (pinfunction "EP_9") (pintype "passive"))
      (node (ref "U5") (pin "1") (pinfunction "TEMP_1") (pintype "input"))
      (node (ref "U5") (pin "3") (pinfunction "GND_3") (pintype "power_in"))
      (node (ref "U5") (pin "9") (pinfunction "EP_9") (pintype "passive"))
      (node (ref "X11") (pin "2") (pintype "passive"))
    )
    (net (code "47") (name "Net-(D1-PadC)") (class "Default")
      (node (ref "D1") (pin "C") (pinfunction "C_C") (pintype "passive"))
      (node (ref "R11") (pin "2") (pinfunction "2_2") (pintype "passive"))
    )
    (net (code "48") (name "Net-(D2-PadC)") (class "Default")
      (node (ref "D2") (pin "C") (pinfunction "C_C") (pintype "passive"))
      (node (ref "R13") (pin "2") (pinfunction "2_2") (pintype "passive"))
    )
    (net (code "49") (name "Net-(D3-PadC)") (class "Default")
      (node (ref "D3") (pin "C") (pinfunction "C_C") (pintype "passive"))
      (node (ref "R15") (pin "2") (pinfunction "2_2") (pintype "passive"))
    )
    (net (code "50") (name "Net-(D4-PadC)") (class "Default")
      (node (ref "D4") (pin "C") (pinfunction "C_C") (pintype "passive"))
      (node (ref "R17") (pin "2") (pinfunction "2_2") (pintype "passive"))
    )
    (net (code "51") (name "Net-(D5-PadC)") (class "Default")
      (node (ref "D5") (pin "C") (pinfunction "C_C") (pintype "passive"))
      (node (ref "R19") (pin "2") (pinfunction "2_2") (pintype "passive"))
    )
    (net (code "52") (name "Net-(D6-PadC)") (class "Default")
      (node (ref "D6") (pin "C") (pinfunction "C_C") (pintype "passive"))
      (node (ref "R12") (pin "2") (pinfunction "2_2") (pintype "passive"))
    )
    (net (code "53") (name "Net-(D7-PadC)") (class "Default")
      (node (ref "D7") (pin "C") (pinfunction "C_C") (pintype "passive"))
      (node (ref "R14") (pin "2") (pinfunction "2_2") (pintype "passive"))
    )
    (net (code "54") (name "Net-(D8-PadC)") (class "Default")
      (node (ref "D8") (pin "C") (pinfunction "C_C") (pintype "passive"))
      (node (ref "R16") (pin "2") (pinfunction "2_2") (pintype "passive"))
    )
    (net (code "55") (name "Net-(D9-PadC)") (class "Default")
      (node (ref "D9") (pin "C") (pinfunction "C_C") (pintype "passive"))
      (node (ref "R18") (pin "2") (pinfunction "2_2") (pintype "passive"))
    )
    (net (code "56") (name "Net-(D10-PadC)") (class "Default")
      (node (ref "D10") (pin "C") (pinfunction "C_C") (pintype "passive"))
      (node (ref "R20") (pin "2") (pinfunction "2_2") (pintype "passive"))
    )
    (net (code "57") (name "Net-(D11-PadC)") (class "Default")
      (node (ref "D11") (pin "C") (pinfunction "C_C") (pintype "passive"))
      (node (ref "R36") (pin "2") (pinfunction "2_2") (pintype "passive"))
    )
    (net (code "58") (name "Net-(D12-PadC)") (class "Default")
      (node (ref "D12") (pin "C") (pinfunction "C_C") (pintype "passive"))
      (node (ref "R38") (pin "2") (pinfunction "2_2") (pintype "passive"))
    )
    (net (code "59") (name "Net-(D13-PadC)") (class "Default")
      (node (ref "D13") (pin "C") (pinfunction "C_C") (pintype "passive"))
      (node (ref "R40") (pin "2") (pinfunction "2_2") (pintype "passive"))
    )
    (net (code "60") (name "Net-(D14-PadC)") (class "Default")
      (node (ref "D14") (pin "C") (pinfunction "C_C") (pintype "passive"))
      (node (ref "R42") (pin "2") (pinfunction "2_2") (pintype "passive"))
    )
    (net (code "61") (name "Net-(D15-PadC)") (class "Default")
      (node (ref "D15") (pin "C") (pinfunction "C_C") (pintype "passive"))
      (node (ref "R44") (pin "2") (pinfunction "2_2") (pintype "passive"))
    )
    (net (code "62") (name "Net-(D16-PadC)") (class "Default")
      (node (ref "D16") (pin "C") (pinfunction "C_C") (pintype "passive"))
      (node (ref "R37") (pin "2") (pinfunction "2_2") (pintype "passive"))
    )
    (net (code "63") (name "Net-(D17-PadC)") (class "Default")
      (node (ref "D17") (pin "C") (pinfunction "C_C") (pintype "passive"))
      (node (ref "R39") (pin "2") (pinfunction "2_2") (pintype "passive"))
    )
    (net (code "64") (name "Net-(D18-PadC)") (class "Default")
      (node (ref "D18") (pin "C") (pinfunction "C_C") (pintype "passive"))
      (node (ref "R41") (pin "2") (pinfunction "2_2") (pintype "passive"))
    )
    (net (code "65") (name "Net-(D19-PadC)") (class "Default")
      (node (ref "D19") (pin "C") (pinfunction "C_C") (pintype "passive"))
      (node (ref "R43") (pin "2") (pinfunction "2_2") (pintype "passive"))
    )
    (net (code "66") (name "Net-(D20-PadC)") (class "Default")
      (node (ref "D20") (pin "C") (pinfunction "C_C") (pintype "passive"))
      (node (ref "R45") (pin "2") (pinfunction "2_2") (pintype "passive"))
    )
    (net (code "67") (name "Net-(D21-A)") (class "Default")
      (node (ref "D21") (pin "2") (pinfunction "A_2") (pintype "passive"))
      (node (ref "L1") (pin "2") (pinfunction "2_2") (pintype "passive"))
      (node (ref "U22") (pin "1") (pinfunction "SW_1") (pintype "output"))
    )
    (net (code "68") (name "Net-(D23-PadC)") (class "Default")
      (node (ref "D23") (pin "C") (pinfunction "C_C") (pintype "passive"))
      (node (ref "R55") (pin "2") (pinfunction "2_2") (pintype "passive"))
    )
    (net (code "69") (name "Net-(D24-PadC)") (class "Default")
      (node (ref "D24") (pin "C") (pinfunction "C_C") (pintype "passive"))
      (node (ref "R56") (pin "2") (pinfunction "2_2") (pintype "passive"))
    )
    (net (code "70") (name "Net-(Q1-D12-Pad1)") (class "Default")
      (node (ref "Q1") (pin "1") (pinfunction "D12_1") (pintype "passive"))
      (node (ref "Q1") (pin "8") (pinfunction "D12_8") (pintype "passive"))
    )
    (net (code "71") (name "Net-(Q1-G1)") (class "Default")
      (node (ref "Q1") (pin "4") (pinfunction "G1_4") (pintype "passive"))
      (node (ref "U6") (pin "3") (pinfunction "OC_3") (pintype "bidirectional"))
    )
    (net (code "72") (name "Net-(Q1-G2)") (class "Default")
      (node (ref "Q1") (pin "5") (pinfunction "G2_5") (pintype "passive"))
      (node (ref "U6") (pin "1") (pinfunction "OD_1") (pintype "bidirectional"))
    )
    (net (code "73") (name "Net-(Q2-D12-Pad1)") (class "Default")
      (node (ref "Q2") (pin "1") (pinfunction "D12_1") (pintype "passive"))
      (node (ref "Q2") (pin "8") (pinfunction "D12_8") (pintype "passive"))
    )
    (net (code "74") (name "Net-(Q2-G1)") (class "Default")
      (node (ref "Q2") (pin "4") (pinfunction "G1_4") (pintype "passive"))
      (node (ref "U7") (pin "3") (pinfunction "OC_3") (pintype "bidirectional"))
    )
    (net (code "75") (name "Net-(Q2-G2)") (class "Default")
      (node (ref "Q2") (pin "5") (pinfunction "G2_5") (pintype "passive"))
      (node (ref "U7") (pin "1") (pinfunction "OD_1") (pintype "bidirectional"))
    )
    (net (code "76") (name "Net-(Q3-D12-Pad1)") (class "Default")
      (node (ref "Q3") (pin "1") (pinfunction "D12_1") (pintype "passive"))
      (node (ref "Q3") (pin "8") (pinfunction "D12_8") (pintype "passive"))
    )
    (net (code "77") (name "Net-(Q3-G1)") (class "Default")
      (node (ref "Q3") (pin "4") (pinfunction "G1_4") (pintype "passive"))
      (node (ref "U8") (pin "3") (pinfunction "OC_3") (pintype "bidirectional"))
    )
    (net (code "78") (name "Net-(Q3-G2)") (class "Default")
      (node (ref "Q3") (pin "5") (pinfunction "G2_5") (pintype "passive"))
      (node (ref "U8") (pin "1") (pinfunction "OD_1") (pintype "bidirectional"))
    )
    (net (code "79") (name "Net-(Q4-D12-Pad1)") (class "Default")
      (node (ref "Q4") (pin "1") (pinfunction "D12_1") (pintype "passive"))
      (node (ref "Q4") (pin "8") (pinfunction "D12_8") (pintype "passive"))
    )
    (net (code "80") (name "Net-(Q4-G1)") (class "Default")
      (node (ref "Q4") (pin "4") (pinfunction "G1_4") (pintype "passive"))
      (node (ref "U9") (pin "3") (pinfunction "OC_3") (pintype "bidirectional"))
    )
    (net (code "81") (name "Net-(Q4-G2)") (class "Default")
      (node (ref "Q4") (pin "5") (pinfunction "G2_5") (pintype "passive"))
      (node (ref "U9") (pin "1") (pinfunction "OD_1") (pintype "bidirectional"))
    )
    (net (code "82") (name "Net-(Q5-D12-Pad1)") (class "Default")
      (node (ref "Q5") (pin "1") (pinfunction "D12_1") (pintype "passive"))
      (node (ref "Q5") (pin "8") (pinfunction "D12_8") (pintype "passive"))
    )
    (net (code "83") (name "Net-(Q5-G1)") (class "Default")
      (node (ref "Q5") (pin "4") (pinfunction "G1_4") (pintype "passive"))
      (node (ref "U10") (pin "3") (pinfunction "OC_3") (pintype "bidirectional"))
    )
    (net (code "84") (name "Net-(Q5-G2)") (class "Default")
      (node (ref "Q5") (pin "5") (pinfunction "G2_5") (pintype "passive"))
      (node (ref "U10") (pin "1") (pinfunction "OD_1") (pintype "bidirectional"))
    )
    (net (code "85") (name "Net-(Q6-D12-Pad1)") (class "Default")
      (node (ref "Q6") (pin "1") (pinfunction "D12_1") (pintype "passive"))
      (node (ref "Q6") (pin "8") (pinfunction "D12_8") (pintype "passive"))
    )
    (net (code "86") (name "Net-(Q6-G1)") (class "Default")
      (node (ref "Q6") (pin "4") (pinfunction "G1_4") (pintype "passive"))
      (node (ref "U16") (pin "3") (pinfunction "OC_3") (pintype "bidirectional"))
    )
    (net (code "87") (name "Net-(Q6-G2)") (class "Default")
      (node (ref "Q6") (pin "5") (pinfunction "G2_5") (pintype "passive"))
      (node (ref "U16") (pin "1") (pinfunction "OD_1") (pintype "bidirectional"))
    )
    (net (code "88") (name "Net-(Q7-D12-Pad1)") (class "Default")
      (node (ref "Q7") (pin "1") (pinfunction "D12_1") (pintype "passive"))
      (node (ref "Q7") (pin "8") (pinfunction "D12_8") (pintype "passive"))
    )
    (net (code "89") (name "Net-(Q7-G1)") (class "Default")
      (node (ref "Q7") (pin "4") (pinfunction "G1_4") (pintype "passive"))
      (node (ref "U17") (pin "3") (pinfunction "OC_3") (pintype "bidirectional"))
    )
    (net (code "90") (name "Net-(Q7-G2)") (class "Default")
      (node (ref "Q7") (pin "5") (pinfunction "G2_5") (pintype "passive"))
      (node (ref "U17") (pin "1") (pinfunction "OD_1") (pintype "bidirectional"))
    )
    (net (code "91") (name "Net-(Q8-D12-Pad1)") (class "Default")
      (node (ref "Q8") (pin "1") (pinfunction "D12_1") (pintype "passive"))
      (node (ref "Q8") (pin "8") (pinfunction "D12_8") (pintype "passive"))
    )
    (net (code "92") (name "Net-(Q8-G1)") (class "Default")
      (node (ref "Q8") (pin "4") (pinfunction "G1_4") (pintype "passive"))
      (node (ref "U18") (pin "3") (pinfunction "OC_3") (pintype "bidirectional"))
    )
    (net (code "93") (name "Net-(Q8-G2)") (class "Default")
      (node (ref "Q8") (pin "5") (pinfunction "G2_5") (pintype "passive"))
      (node (ref "U18") (pin "1") (pinfunction "OD_1") (pintype "bidirectional"))
    )
    (net (code "94") (name "Net-(Q9-D12-Pad1)") (class "Default")
      (node (ref "Q9") (pin "1") (pinfunction "D12_1") (pintype "passive"))
      (node (ref "Q9") (pin "8") (pinfunction "D12_8") (pintype "passive"))
    )
    (net (code "95") (name "Net-(Q9-G1)") (class "Default")
      (node (ref "Q9") (pin "4") (pinfunction "G1_4") (pintype "passive"))
      (node (ref "U19") (pin "3") (pinfunction "OC_3") (pintype "bidirectional"))
    )
    (net (code "96") (name "Net-(Q9-G2)") (class "Default")
      (node (ref "Q9") (pin "5") (pinfunction "G2_5") (pintype "passive"))
      (node (ref "U19") (pin "1") (pinfunction "OD_1") (pintype "bidirectional"))
    )
    (net (code "97") (name "Net-(Q10-D12-Pad1)") (class "Default")
      (node (ref "Q10") (pin "1") (pinfunction "D12_1") (pintype "passive"))
      (node (ref "Q10") (pin "8") (pinfunction "D12_8") (pintype "passive"))
    )
    (net (code "98") (name "Net-(Q10-G1)") (class "Default")
      (node (ref "Q10") (pin "4") (pinfunction "G1_4") (pintype "passive"))
      (node (ref "U20") (pin "3") (pinfunction "OC_3") (pintype "bidirectional"))
    )
    (net (code "99") (name "Net-(Q10-G2)") (class "Default")
      (node (ref "Q10") (pin "5") (pinfunction "G2_5") (pintype "passive"))
      (node (ref "U20") (pin "1") (pinfunction "OD_1") (pintype "bidirectional"))
    )
    (net (code "100") (name "Net-(Q11-D12-Pad1)") (class "Default")
      (node (ref "Q11") (pin "1") (pinfunction "D12_1") (pintype "passive"))
      (node (ref "Q11") (pin "8") (pinfunction "D12_8") (pintype "passive"))
    )
    (net (code "101") (name "Net-(Q11-G1)") (class "Default")
      (node (ref "Q11") (pin "4") (pinfunction "G1_4") (pintype "passive"))
      (node (ref "U23") (pin "3") (pinfunction "OC_3") (pintype "bidirectional"))
    )
    (net (code "102") (name "Net-(Q11-G2)") (class "Default")
      (node (ref "Q11") (pin "5") (pinfunction "G2_5") (pintype "passive"))
      (node (ref "U23") (pin "1") (pinfunction "OD_1") (pintype "bidirectional"))
    )
    (net (code "103") (name "Net-(U1-PROG)") (class "Default")
      (node (ref "R1") (pin "2") (pinfunction "2_2") (pintype "passive"))
      (node (ref "U1") (pin "2") (pinfunction "PROG_2") (pintype "bidirectional"))
    )
    (net (code "104") (name "Net-(U2-PROG)") (class "Default")
      (node (ref "R2") (pin "2") (pinfunction "2_2") (pintype "passive"))
      (node (ref "U2") (pin "2") (pinfunction "PROG_2") (pintype "bidirectional"))
    )
    (net (code "105") (name "Net-(U3-PROG)") (class "Default")
      (node (ref "R3") (pin "2") (pinfunction "2_2") (pintype "passive"))
      (node (ref "U3") (pin "2") (pinfunction "PROG_2") (pintype "bidirectional"))
    )
    (net (code "106") (name "Net-(U4-PROG)") (class "Default")
      (node (ref "R4") (pin "2") (pinfunction "2_2") (pintype "passive"))
      (node (ref "U4") (pin "2") (pinfunction "PROG_2") (pintype "bidirectional"))
    )
    (net (code "107") (name "Net-(U5-PROG)") (class "Default")
      (node (ref "R5") (pin "2") (pinfunction "2_2") (pintype "passive"))
      (node (ref "U5") (pin "2") (pinfunction "PROG_2") (pintype "bidirectional"))
    )
    (net (code "108") (name "Net-(U6-CS)") (class "Default")
      (node (ref "R21") (pin "2") (pinfunction "2_2") (pintype "passive"))
      (node (ref "U6") (pin "2") (pinfunction "CS_2") (pintype "bidirectional"))
    )
    (net (code "109") (name "Net-(U6-VCC)") (class "Default")
      (node (ref "C13") (pin "2") (pinfunction "2_2") (pintype "passive"))
      (node (ref "R9") (pin "1") (pinfunction "1_1") (pintype "passive"))
      (node (ref "U6") (pin "5") (pinfunction "VCC_5") (pintype "power_in"))
    )
    (net (code "110") (name "Net-(U7-CS)") (class "Default")
      (node (ref "R22") (pin "2") (pinfunction "2_2") (pintype "passive"))
      (node (ref "U7") (pin "2") (pinfunction "CS_2") (pintype "bidirectional"))
    )
    (net (code "111") (name "Net-(U7-VCC)") (class "Default")
      (node (ref "C14") (pin "2") (pinfunction "2_2") (pintype "passive"))
      (node (ref "R10") (pin "1") (pinfunction "1_1") (pintype "passive"))
      (node (ref "U7") (pin "5") (pinfunction "VCC_5") (pintype "power_in"))
    )
    (net (code "112") (name "Net-(U8-CS)") (class "Default")
      (node (ref "R23") (pin "2") (pinfunction "2_2") (pintype "passive"))
      (node (ref "U8") (pin "2") (pinfunction "CS_2") (pintype "bidirectional"))
    )
    (net (code "113") (name "Net-(U8-VCC)") (class "Default")
      (node (ref "C15") (pin "2") (pinfunction "2_2") (pintype "passive"))
      (node (ref "R6") (pin "1") (pinfunction "1_1") (pintype "passive"))
      (node (ref "U8") (pin "5") (pinfunction "VCC_5") (pintype "power_in"))
    )
    (net (code "114") (name "Net-(U9-CS)") (class "Default")
      (node (ref "R24") (pin "2") (pinfunction "2_2") (pintype "passive"))
      (node (ref "U9") (pin "2") (pinfunction "CS_2") (pintype "bidirectional"))
    )
    (net (code "115") (name "Net-(U9-VCC)") (class "Default")
      (node (ref "C11") (pin "2") (pinfunction "2_2") (pintype "passive"))
      (node (ref "R7") (pin "1") (pinfunction "1_1") (pintype "passive"))
      (node (ref "U9") (pin "5") (pinfunction "VCC_5") (pintype "power_in"))
    )
    (net (code "116") (name "Net-(U10-CS)") (class "Default")
      (node (ref "R25") (pin "2") (pinfunction "2_2") (pintype "passive"))
      (node (ref "U10") (pin "2") (pinfunction "CS_2") (pintype "bidirectional"))
    )
    (net (code "117") (name "Net-(U10-VCC)") (class "Default")
      (node (ref "C12") (pin "2") (pinfunction "2_2") (pintype "passive"))
      (node (ref "R8") (pin "1") (pinfunction "1_1") (pintype "passive"))
      (node (ref "U10") (pin "5") (pinfunction "VCC_5") (pintype "power_in"))
    )
    (net (code "118") (name "Net-(U11-PROG)") (class "Default")
      (node (ref "R26") (pin "2") (pinfunction "2_2") (pintype "passive"))
      (node (ref "U11") (pin "2") (pinfunction "PROG_2") (pintype "bidirectional"))
    )
    (net (code "119") (name "Net-(U12-PROG)") (class "Default")
      (node (ref "R27") (pin "2") (pinfunction "2_2") (pintype "passive"))
      (node (ref "U12") (pin "2") (pinfunction "PROG_2") (pintype "bidirectional"))
    )
    (net (code "120") (name "Net-(U13-PROG)") (class "Default")
      (node (ref "R28") (pin "2") (pinfunction "2_2") (pintype "passive"))
      (node (ref "U13") (pin "2") (pinfunction "PROG_2") (pintype "bidirectional"))
    )
    (net (code "121") (name "Net-(U14-PROG)") (class "Default")
      (node (ref "R29") (pin "2") (pinfunction "2_2") (pintype "passive"))
      (node (ref "U14") (pin "2") (pinfunction "PROG_2") (pintype "bidirectional"))
    )
    (net (code "122") (name "Net-(U15-PROG)") (class "Default")
      (node (ref "R30") (pin "2") (pinfunction "2_2") (pintype "passive"))
      (node (ref "U15") (pin "2") (pinfunction "PROG_2") (pintype "bidirectional"))
    )
    (net (code "123") (name "Net-(U16-CS)") (class "Default")
      (node (ref "R46") (pin "2") (pinfunction "2_2") (pintype "passive"))
      (node (ref "U16") (pin "2") (pinfunction "CS_2") (pintype "bidirectional"))
    )
    (net (code "124") (name "Net-(U16-VCC)") (class "Default")
      (node (ref "C26") (pin "2") (pinfunction "2_2") (pintype "passive"))
      (node (ref "R31") (pin "1") (pinfunction "1_1") (pintype "passive"))
      (node (ref "U16") (pin "5") (pinfunction "VCC_5") (pintype "power_in"))
    )
    (net (code "125") (name "Net-(U17-CS)") (class "Default")
      (node (ref "R47") (pin "2") (pinfunction "2_2") (pintype "passive"))
      (node (ref "U17") (pin "2") (pinfunction "CS_2") (pintype "bidirectional"))
    )
    (net (code "126") (name "Net-(U17-VCC)") (class "Default")
      (node (ref "C27") (pin "2") (pinfunction "2_2") (pintype "passive"))
      (node (ref "R32") (pin "1") (pinfunction "1_1") (pintype "passive"))
      (node (ref "U17") (pin "5") (pinfunction "VCC_5") (pintype "power_in"))
    )
    (net (code "127") (name "Net-(U18-CS)") (class "Default")
      (node (ref "R48") (pin "2") (pinfunction "2_2") (pintype "passive"))
      (node (ref "U18") (pin "2") (pinfunction "CS_2") (pintype "bidirectional"))
    )
    (net (code "128") (name "Net-(U18-VCC)") (class "Default")
      (node (ref "C28") (pin "2") (pinfunction "2_2") (pintype "passive"))
      (node (ref "R33") (pin "1") (pinfunction "1_1") (pintype "passive"))
      (node (ref "U18") (pin "5") (pinfunction "VCC_5") (pintype "power_in"))
    )
    (net (code "129") (name "Net-(U19-CS)") (class "Default")
      (node (ref "R49") (pin "2") (pinfunction "2_2") (pintype "passive"))
      (node (ref "U19") (pin "2") (pinfunction "CS_2") (pintype "bidirectional"))
    )
    (net (code "130") (name "Net-(U19-VCC)") (class "Default")
      (node (ref "C29") (pin "2") (pinfunction "2_2") (pintype "passive"))
      (node (ref "R34") (pin "1") (pinfunction "1_1") (pintype "passive"))
      (node (ref "U19") (pin "5") (pinfunction "VCC_5") (pintype "power_in"))
    )
    (net (code "131") (name "Net-(U20-CS)") (class "Default")
      (node (ref "R50") (pin "2") (pinfunction "2_2") (pintype "passive"))
      (node (ref "U20") (pin "2") (pinfunction "CS_2") (pintype "bidirectional"))
    )
    (net (code "132") (name "Net-(U20-VCC)") (class "Default")
      (node (ref "C30") (pin "2") (pinfunction "2_2") (pintype "passive"))
      (node (ref "R35") (pin "1") (pinfunction "1_1") (pintype "passive"))
      (node (ref "U20") (pin "5") (pinfunction "VCC_5") (pintype "power_in"))
    )
    (net (code "133") (name "Net-(U21-PROG)") (class "Default")
      (node (ref "R51") (pin "2") (pinfunction "2_2") (pintype "passive"))
      (node (ref "U21") (pin "2") (pinfunction "PROG_2") (pintype "bidirectional"))
    )
    (net (code "134") (name "Net-(U22-EN)") (class "Default")
      (node (ref "C32") (pin "2") (pinfunction "2_2") (pintype "passive"))
      (node (ref "L1") (pin "1") (pinfunction "1_1") (pintype "passive"))
      (node (ref "U22") (pin "4") (pinfunction "EN_4") (pintype "input"))
      (node (ref "U22") (pin "5") (pinfunction "IN_5") (pintype "input"))
      (node (ref "X12") (pin "1") (pintype "passive"))
    )
    (net (code "135") (name "Net-(U22-FB)") (class "Default")
      (node (ref "R52") (pin "1") (pinfunction "1_1") (pintype "passive"))
      (node (ref "R53") (pin "2") (pinfunction "2_2") (pintype "passive"))
      (node (ref "U22") (pin "3") (pinfunction "FB_3") (pintype "input"))
    )
    (net (code "136") (name "Net-(U23-CS)") (class "Default")
      (node (ref "R57") (pin "2") (pinfunction "2_2") (pintype "passive"))
      (node (ref "U23") (pin "2") (pinfunction "CS_2") (pintype "bidirectional"))
    )
    (net (code "137") (name "Net-(U23-VCC)") (class "Default")
      (node (ref "C35") (pin "2") (pinfunction "2_2") (pintype "passive"))
      (node (ref "R54") (pin "1") (pinfunction "1_1") (pintype "passive"))
      (node (ref "U23") (pin "5") (pinfunction "VCC_5") (pintype "power_in"))
    )
    (net (code "138") (name "Vin") (class "Default")
      (node (ref "C31") (pin "2") (pinfunction "2_2") (pintype "passive"))
      (node (ref "D22") (pin "1") (pinfunction "K_1") (pintype "passive"))
      (node (ref "U21") (pin "4") (pinfunction "VCC_4") (pintype "power_in"))
      (node (ref "U21") (pin "8") (pinfunction "CE_8") (pintype "input"))
      (node (ref "X11") (pin "1") (pintype "passive"))
      (node (ref "X12") (pin "2") (pintype "passive"))
    )
    (net (code "139") (name "unconnected-(U6-TD-Pad4)") (class "Default")
      (node (ref "U6") (pin "4") (pinfunction "TD_4") (pintype "bidirectional"))
    )
    (net (code "140") (name "unconnected-(U7-TD-Pad4)") (class "Default")
      (node (ref "U7") (pin "4") (pinfunction "TD_4") (pintype "bidirectional"))
    )
    (net (code "141") (name "unconnected-(U8-TD-Pad4)") (class "Default")
      (node (ref "U8") (pin "4") (pinfunction "TD_4") (pintype "bidirectional"))
    )
    (net (code "142") (name "unconnected-(U9-TD-Pad4)") (class "Default")
      (node (ref "U9") (pin "4") (pinfunction "TD_4") (pintype "bidirectional"))
    )
    (net (code "143") (name "unconnected-(U10-TD-Pad4)") (class "Default")
      (node (ref "U10") (pin "4") (pinfunction "TD_4") (pintype "bidirectional"))
    )
    (net (code "144") (name "unconnected-(U16-TD-Pad4)") (class "Default")
      (node (ref "U16") (pin "4") (pinfunction "TD_4") (pintype "bidirectional"))
    )
    (net (code "145") (name "unconnected-(U17-TD-Pad4)") (class "Default")
      (node (ref "U17") (pin "4") (pinfunction "TD_4") (pintype "bidirectional"))
    )
    (net (code "146") (name "unconnected-(U18-TD-Pad4)") (class "Default")
      (node (ref "U18") (pin "4") (pinfunction "TD_4") (pintype "bidirectional"))
    )
    (net (code "147") (name "unconnected-(U19-TD-Pad4)") (class "Default")
      (node (ref "U19") (pin "4") (pinfunction "TD_4") (pintype "bidirectional"))
    )
    (net (code "148") (name "unconnected-(U20-TD-Pad4)") (class "Default")
      (node (ref "U20") (pin "4") (pinfunction "TD_4") (pintype "bidirectional"))
    )
    (net (code "149") (name "unconnected-(U23-TD-Pad4)") (class "Default")
      (node (ref "U23") (pin "4") (pinfunction "TD_4") (pintype "bidirectional"))
    )
    (net (code "150") (name "unconnected-(U24-3V3-PadJ2-1)") (class "Default")
      (node (ref "U24") (pin "J2-1") (pinfunction "3V3_J2-1") (pintype "power_in+no_connect"))
    )
    (net (code "151") (name "unconnected-(U24-CLK-PadJ3-19)") (class "Default")
      (node (ref "U24") (pin "J3-19") (pinfunction "CLK_J3-19") (pintype "input+no_connect"))
    )
    (net (code "152") (name "unconnected-(U24-CMD-PadJ2-18)") (class "Default")
      (node (ref "U24") (pin "J2-18") (pinfunction "CMD_J2-18") (pintype "bidirectional+no_connect"))
    )
    (net (code "153") (name "unconnected-(U24-EN-PadJ2-2)") (class "Default")
      (node (ref "U24") (pin "J2-2") (pinfunction "EN_J2-2") (pintype "input+no_connect"))
    )
    (net (code "154") (name "unconnected-(U24-IO0-PadJ3-14)") (class "Default")
      (node (ref "U24") (pin "J3-14") (pinfunction "IO0_J3-14") (pintype "bidirectional+no_connect"))
    )
    (net (code "155") (name "unconnected-(U24-IO2-PadJ3-15)") (class "Default")
      (node (ref "U24") (pin "J3-15") (pinfunction "IO2_J3-15") (pintype "bidirectional+no_connect"))
    )
    (net (code "156") (name "unconnected-(U24-IO4-PadJ3-13)") (class "Default")
      (node (ref "U24") (pin "J3-13") (pinfunction "IO4_J3-13") (pintype "bidirectional+no_connect"))
    )
    (net (code "157") (name "unconnected-(U24-IO5-PadJ3-10)") (class "Default")
      (node (ref "U24") (pin "J3-10") (pinfunction "IO5_J3-10") (pintype "bidirectional+no_connect"))
    )
    (net (code "158") (name "unconnected-(U24-IO12-PadJ2-13)") (class "Default")
      (node (ref "U24") (pin "J2-13") (pinfunction "IO12_J2-13") (pintype "bidirectional+no_connect"))
    )
    (net (code "159") (name "unconnected-(U24-IO13-PadJ2-15)") (class "Default")
      (node (ref "U24") (pin "J2-15") (pinfunction "IO13_J2-15") (pintype "bidirectional+no_connect"))
    )
    (net (code "160") (name "unconnected-(U24-IO14-PadJ2-12)") (class "Default")
      (node (ref "U24") (pin "J2-12") (pinfunction "IO14_J2-12") (pintype "bidirectional+no_connect"))
    )
    (net (code "161") (name "unconnected-(U24-IO15-PadJ3-16)") (class "Default")
      (node (ref "U24") (pin "J3-16") (pinfunction "IO15_J3-16") (pintype "bidirectional+no_connect"))
    )
    (net (code "162") (name "unconnected-(U24-IO16-PadJ3-12)") (class "Default")
      (node (ref "U24") (pin "J3-12") (pinfunction "IO16_J3-12") (pintype "bidirectional+no_connect"))
    )
    (net (code "163") (name "unconnected-(U24-IO17-PadJ3-11)") (class "Default")
      (node (ref "U24") (pin "J3-11") (pinfunction "IO17_J3-11") (pintype "bidirectional+no_connect"))
    )
    (net (code "164") (name "unconnected-(U24-IO18-PadJ3-9)") (class "Default")
      (node (ref "U24") (pin "J3-9") (pinfunction "IO18_J3-9") (pintype "bidirectional+no_connect"))
    )
    (net (code "165") (name "unconnected-(U24-IO19-PadJ3-8)") (class "Default")
      (node (ref "U24") (pin "J3-8") (pinfunction "IO19_J3-8") (pintype "bidirectional+no_connect"))
    )
    (net (code "166") (name "unconnected-(U24-IO21-PadJ3-6)") (class "Default")
      (node (ref "U24") (pin "J3-6") (pinfunction "IO21_J3-6") (pintype "bidirectional+no_connect"))
    )
    (net (code "167") (name "unconnected-(U24-IO22-PadJ3-3)") (class "Default")
      (node (ref "U24") (pin "J3-3") (pinfunction "IO22_J3-3") (pintype "bidirectional+no_connect"))
    )
    (net (code "168") (name "unconnected-(U24-IO23-PadJ3-2)") (class "Default")
      (node (ref "U24") (pin "J3-2") (pinfunction "IO23_J3-2") (pintype "bidirectional+no_connect"))
    )
    (net (code "169") (name "unconnected-(U24-IO25-PadJ2-9)") (class "Default")
      (node (ref "U24") (pin "J2-9") (pinfunction "IO25_J2-9") (pintype "bidirectional+no_connect"))
    )
    (net (code "170") (name "unconnected-(U24-IO26-PadJ2-10)") (class "Default")
      (node (ref "U24") (pin "J2-10") (pinfunction "IO26_J2-10") (pintype "bidirectional+no_connect"))
    )
    (net (code "171") (name "unconnected-(U24-IO27-PadJ2-11)") (class "Default")
      (node (ref "U24") (pin "J2-11") (pinfunction "IO27_J2-11") (pintype "bidirectional+no_connect"))
    )
    (net (code "172") (name "unconnected-(U24-IO32-PadJ2-7)") (class "Default")
      (node (ref "U24") (pin "J2-7") (pinfunction "IO32_J2-7") (pintype "bidirectional+no_connect"))
    )
    (net (code "173") (name "unconnected-(U24-IO33-PadJ2-8)") (class "Default")
      (node (ref "U24") (pin "J2-8") (pinfunction "IO33_J2-8") (pintype "bidirectional+no_connect"))
    )
    (net (code "174") (name "unconnected-(U24-IO34-PadJ2-5)") (class "Default")
      (node (ref "U24") (pin "J2-5") (pinfunction "IO34_J2-5") (pintype "bidirectional+no_connect"))
    )
    (net (code "175") (name "unconnected-(U24-IO35-PadJ2-6)") (class "Default")
      (node (ref "U24") (pin "J2-6") (pinfunction "IO35_J2-6") (pintype "bidirectional+no_connect"))
    )
    (net (code "176") (name "unconnected-(U24-RXD0-PadJ3-5)") (class "Default")
      (node (ref "U24") (pin "J3-5") (pinfunction "RXD0_J3-5") (pintype "input+no_connect"))
    )
    (net (code "177") (name "unconnected-(U24-SD0-PadJ3-18)") (class "Default")
      (node (ref "U24") (pin "J3-18") (pinfunction "SD0_J3-18") (pintype "bidirectional+no_connect"))
    )
    (net (code "178") (name "unconnected-(U24-SD1-PadJ3-17)") (class "Default")
      (node (ref "U24") (pin "J3-17") (pinfunction "SD1_J3-17") (pintype "bidirectional+no_connect"))
    )
    (net (code "179") (name "unconnected-(U24-SD2-PadJ2-16)") (class "Default")
      (node (ref "U24") (pin "J2-16") (pinfunction "SD2_J2-16") (pintype "bidirectional+no_connect"))
    )
    (net (code "180") (name "unconnected-(U24-SD3-PadJ2-17)") (class "Default")
      (node (ref "U24") (pin "J2-17") (pinfunction "SD3_J2-17") (pintype "bidirectional+no_connect"))
    )
    (net (code "181") (name "unconnected-(U24-SENSOR_VN-PadJ2-4)") (class "Default")
      (node (ref "U24") (pin "J2-4") (pinfunction "SENSOR_VN_J2-4") (pintype "input+no_connect"))
    )
    (net (code "182") (name "unconnected-(U24-SENSOR_VP-PadJ2-3)") (class "Default")
      (node (ref "U24") (pin "J2-3") (pinfunction "SENSOR_VP_J2-3") (pintype "input+no_connect"))
    )
    (net (code "183") (name "unconnected-(U24-TXD0-PadJ3-4)") (class "Default")
      (node (ref "U24") (pin "J3-4") (pinfunction "TXD0_J3-4") (pintype "output+no_connect"))
    )
  )
)
